# avocado-rev01.net
KiCad netlist of a schematic drawn in EAGLE
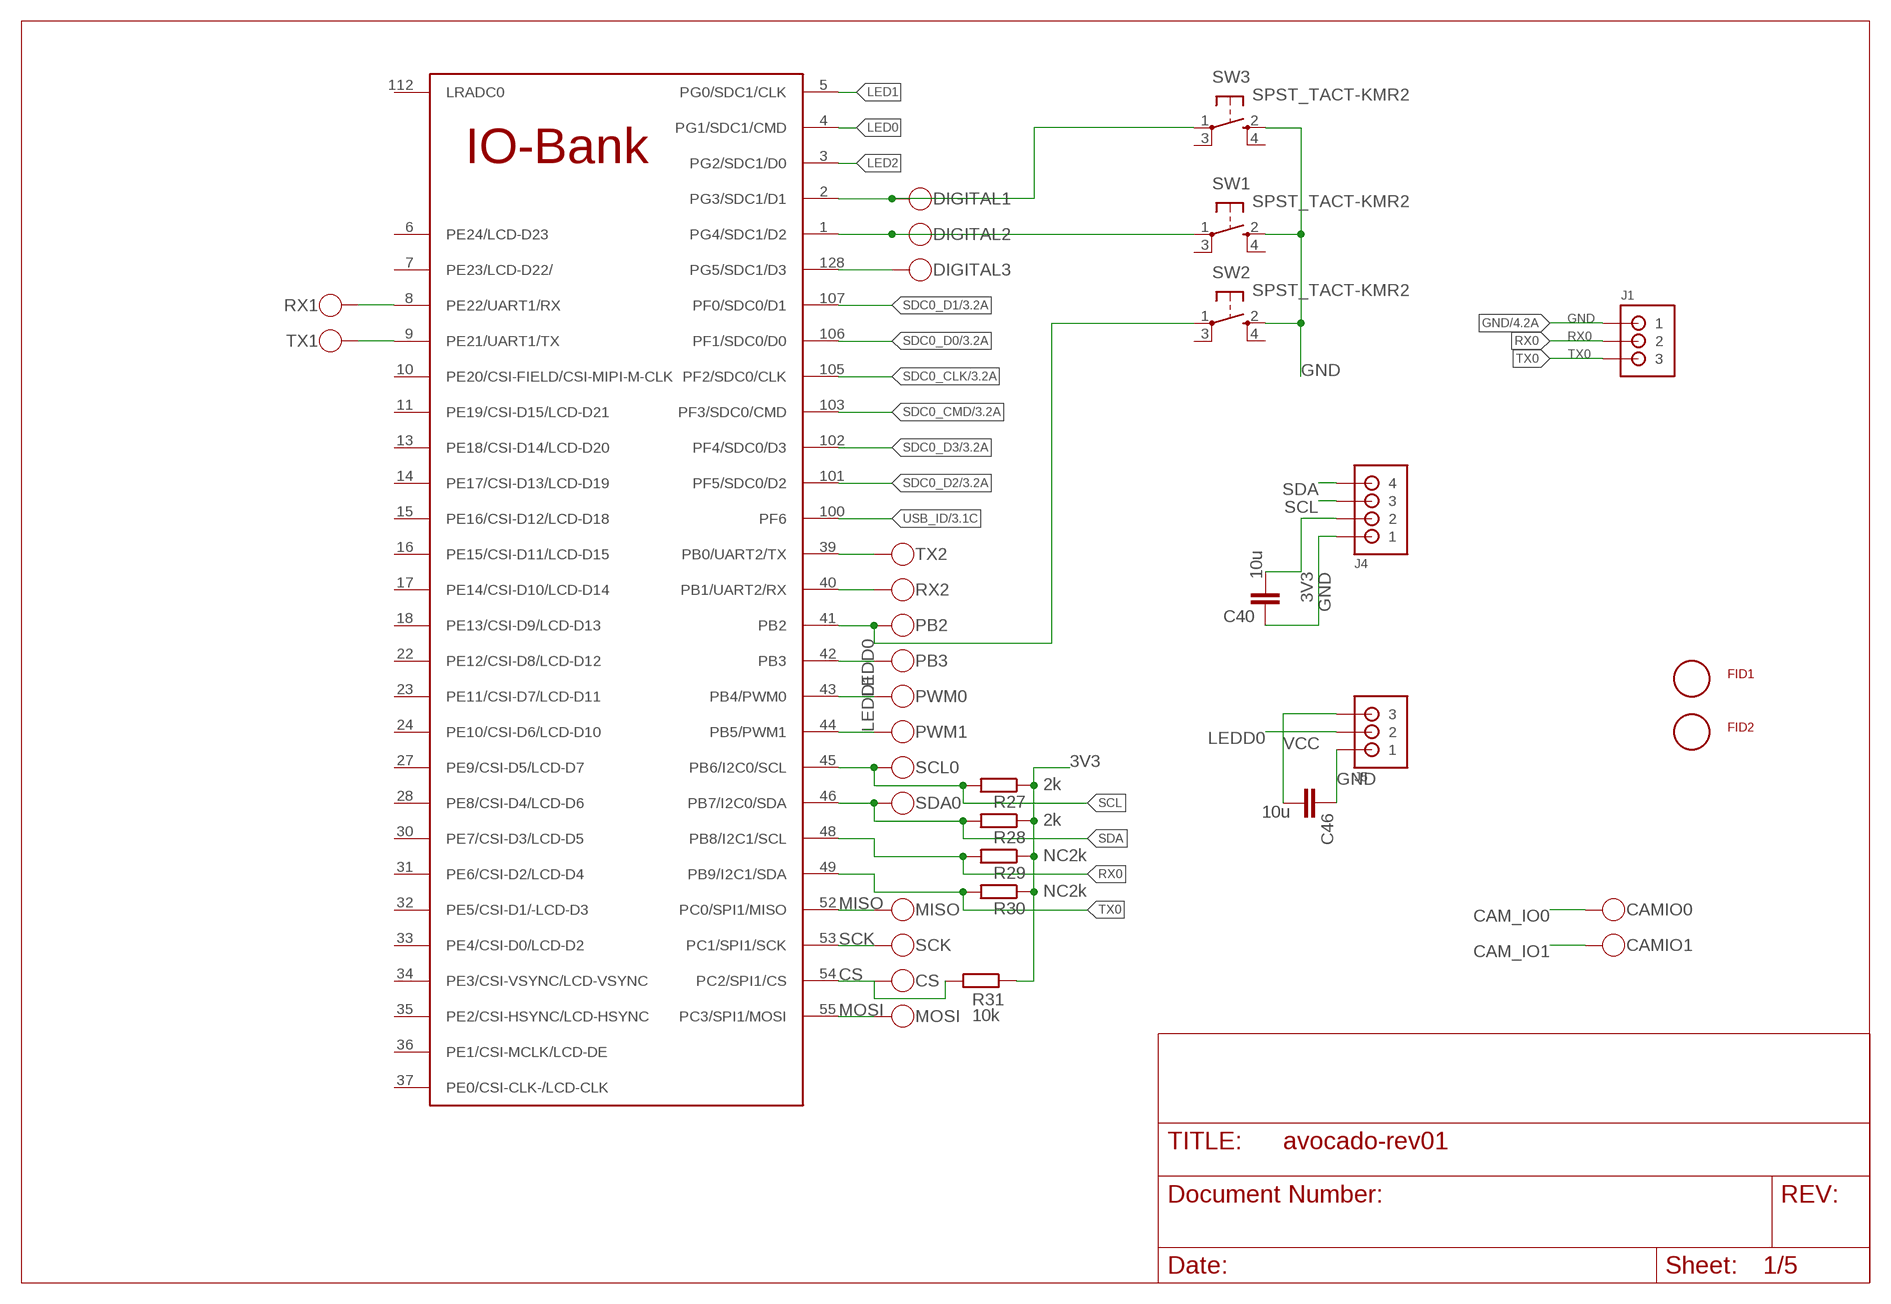
[diagram p0: schematic, sheet 1]
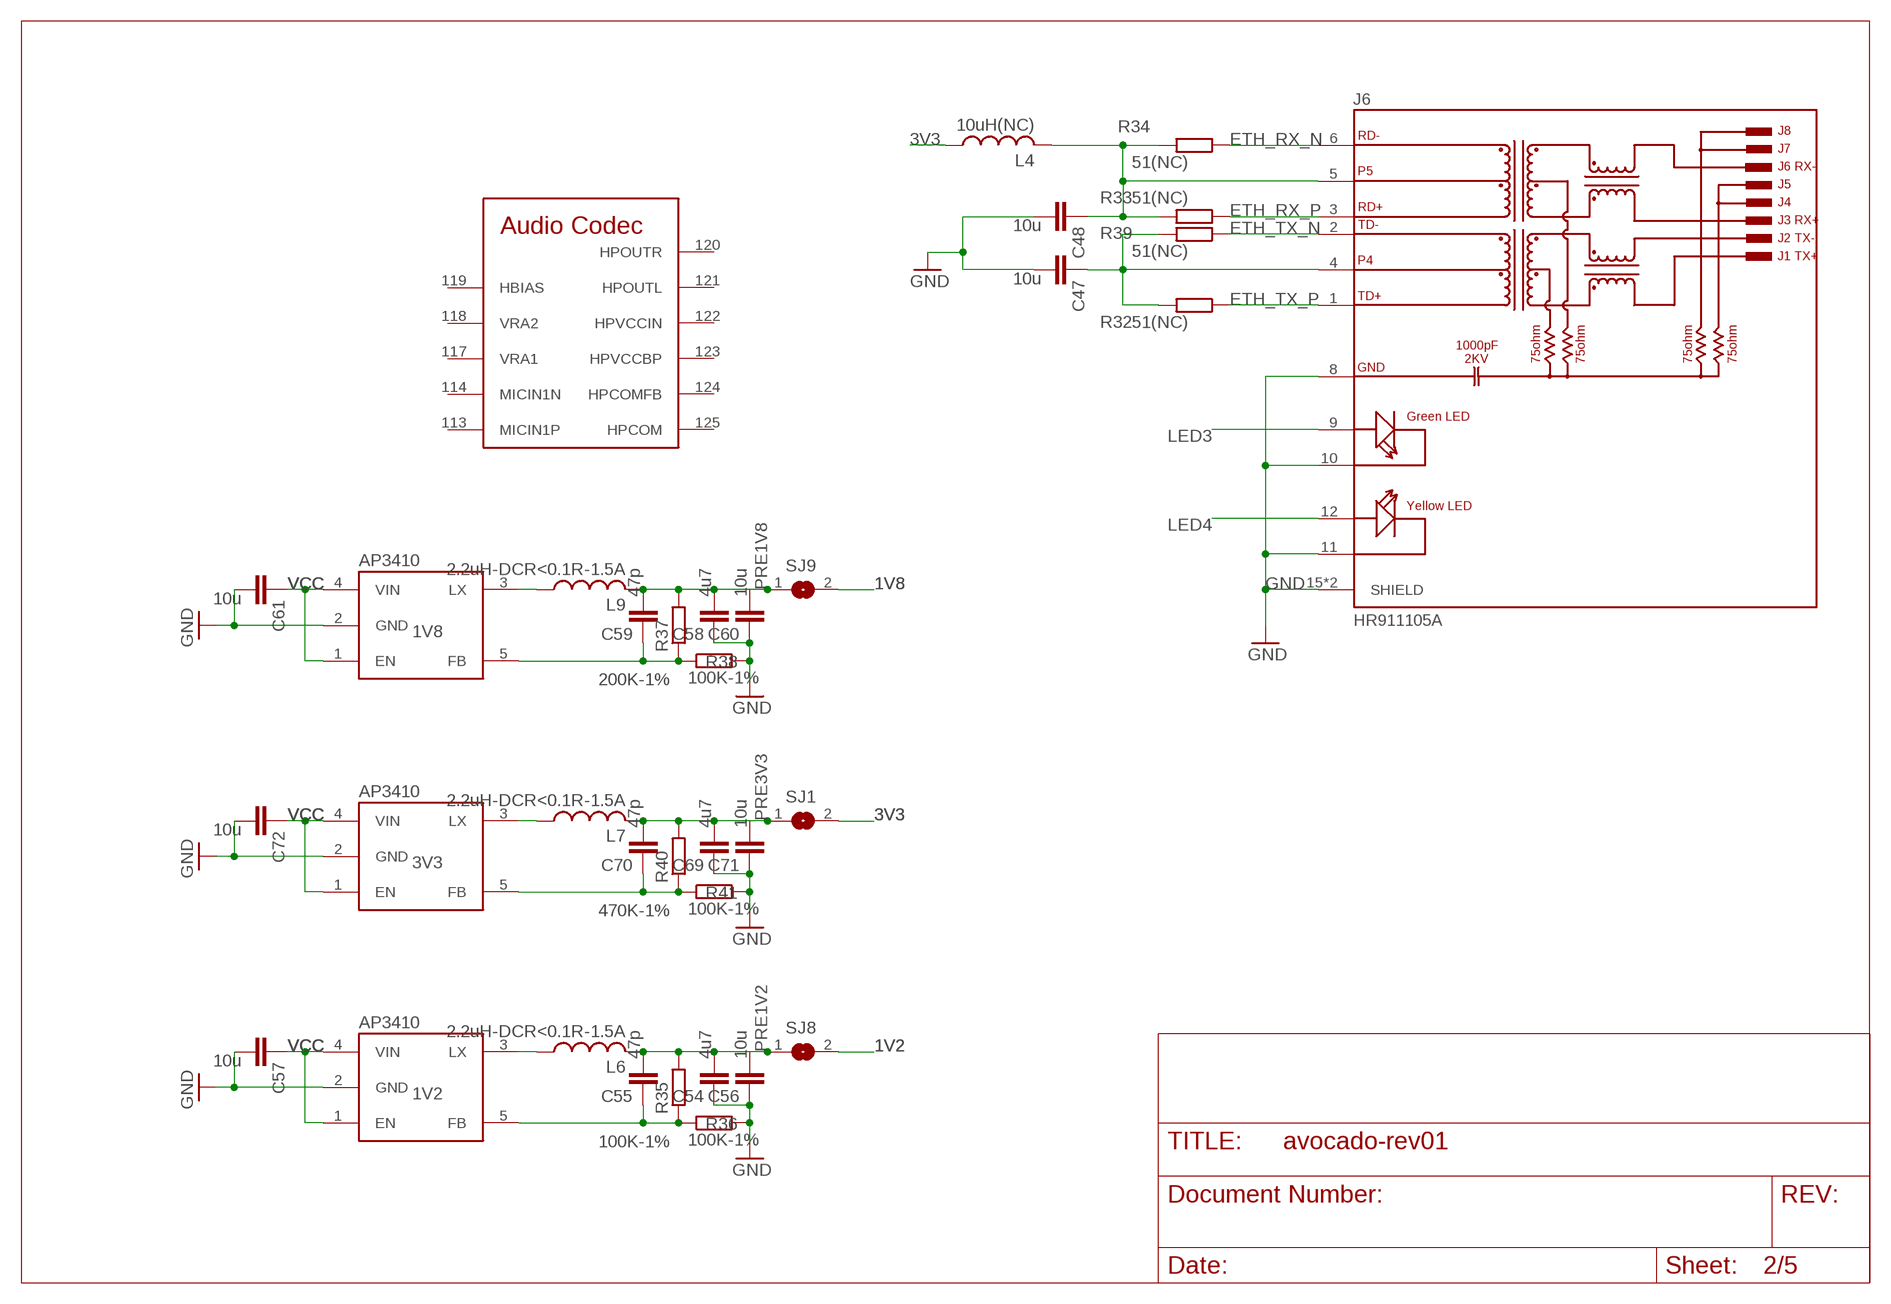
[diagram p1: schematic, sheet 2]
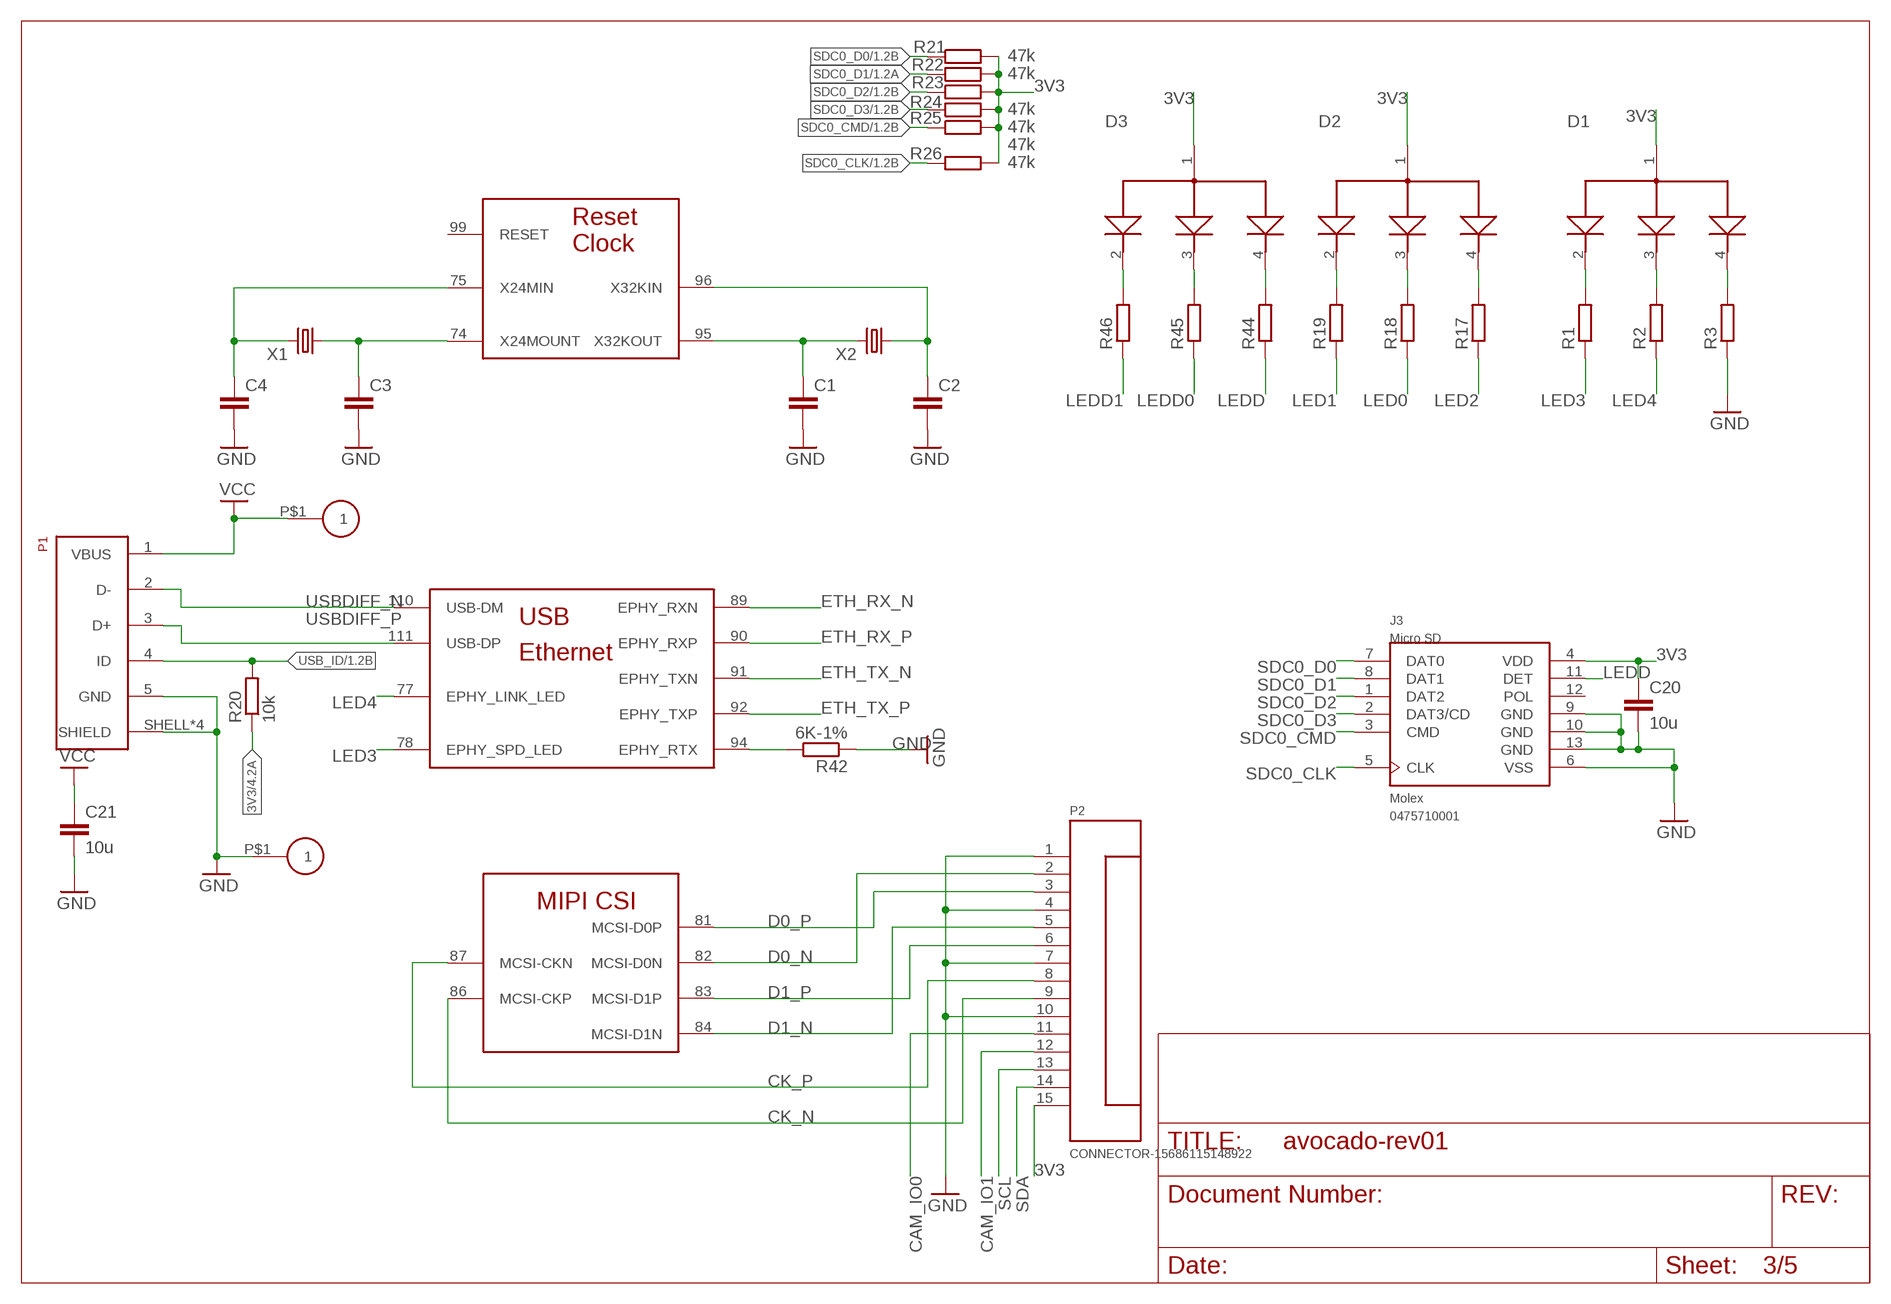
[diagram p2: schematic, sheet 3]
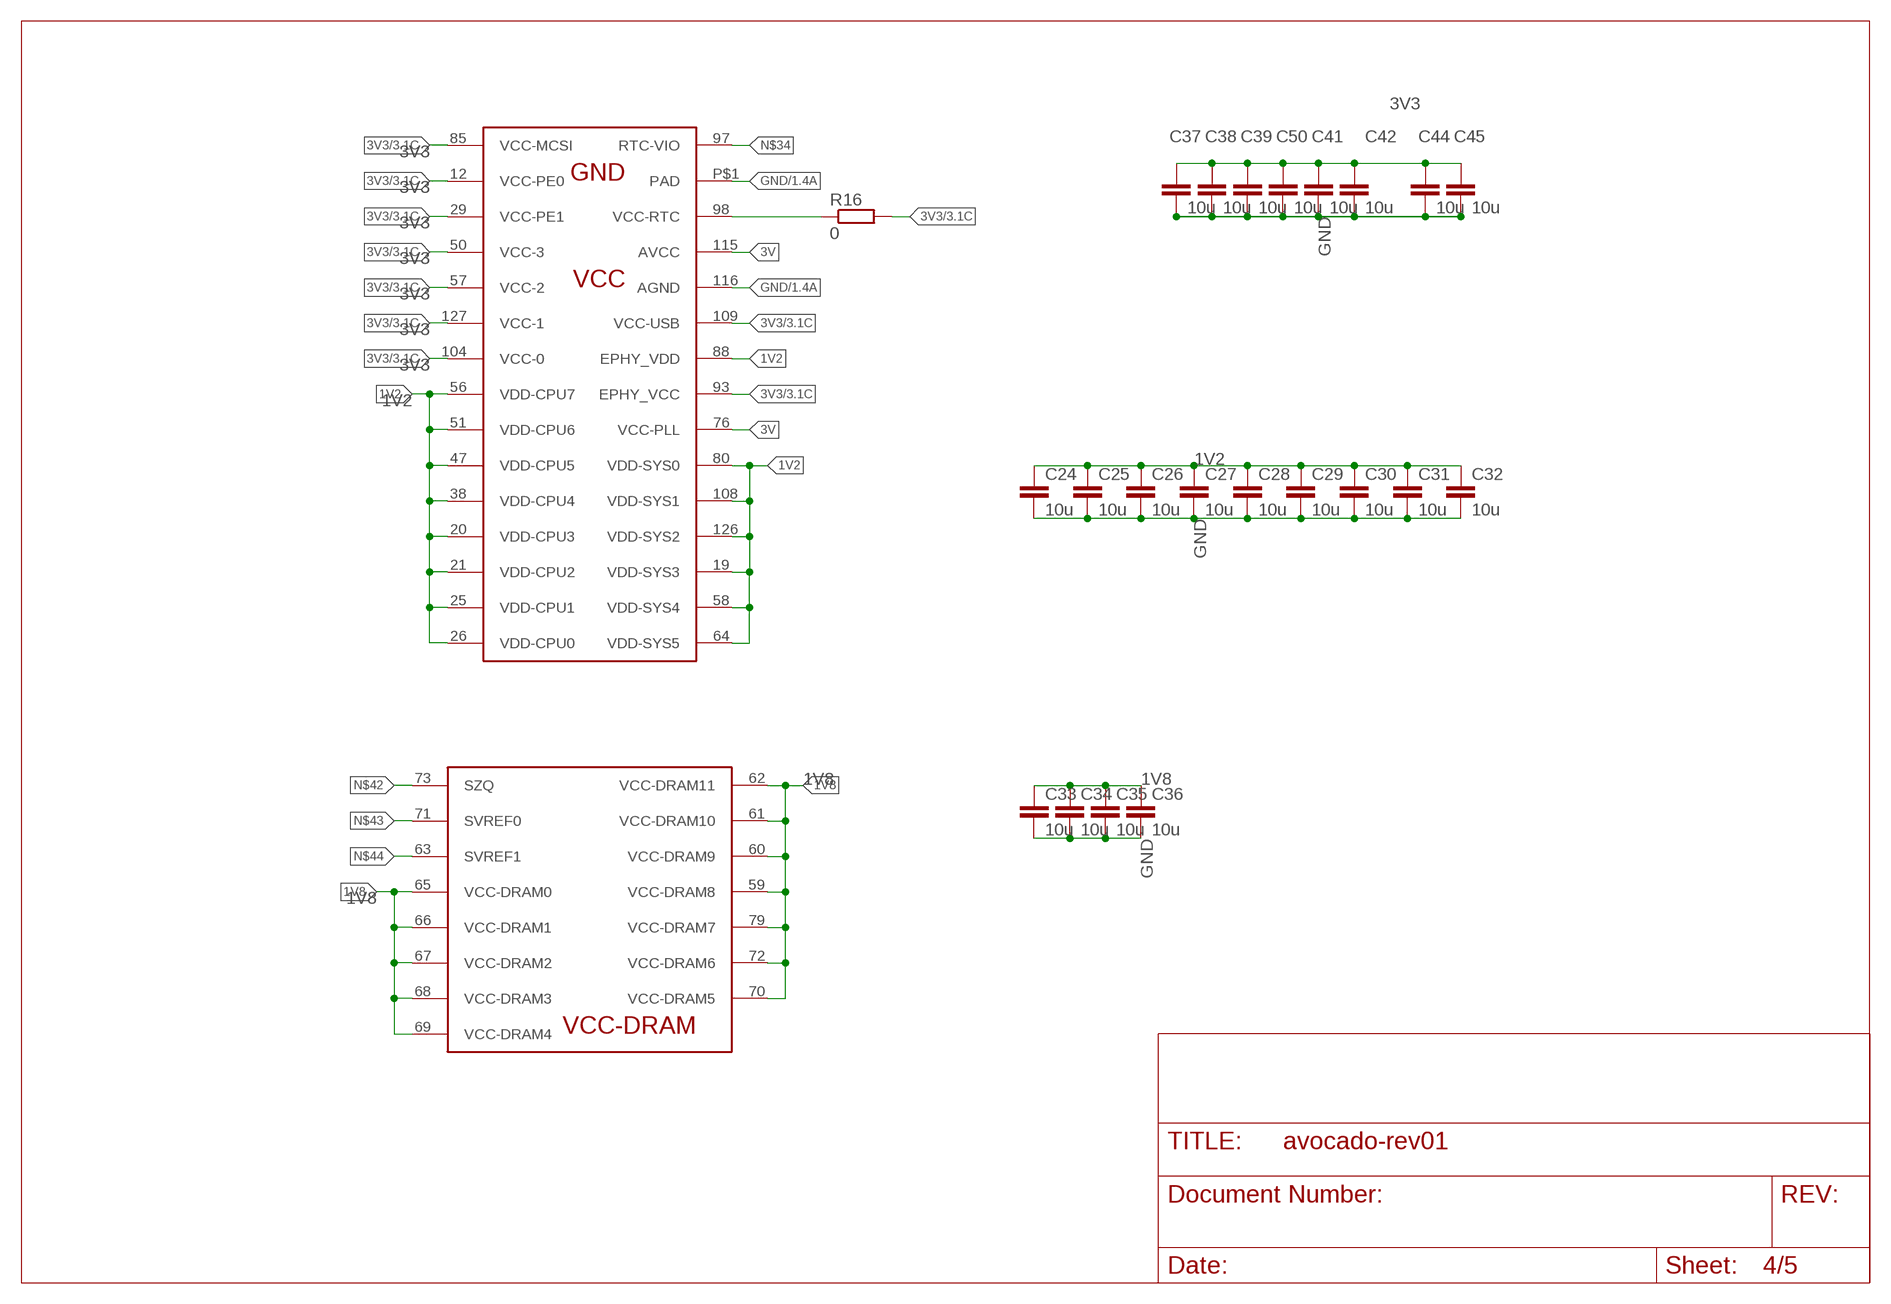
[diagram p3: schematic, sheet 4]
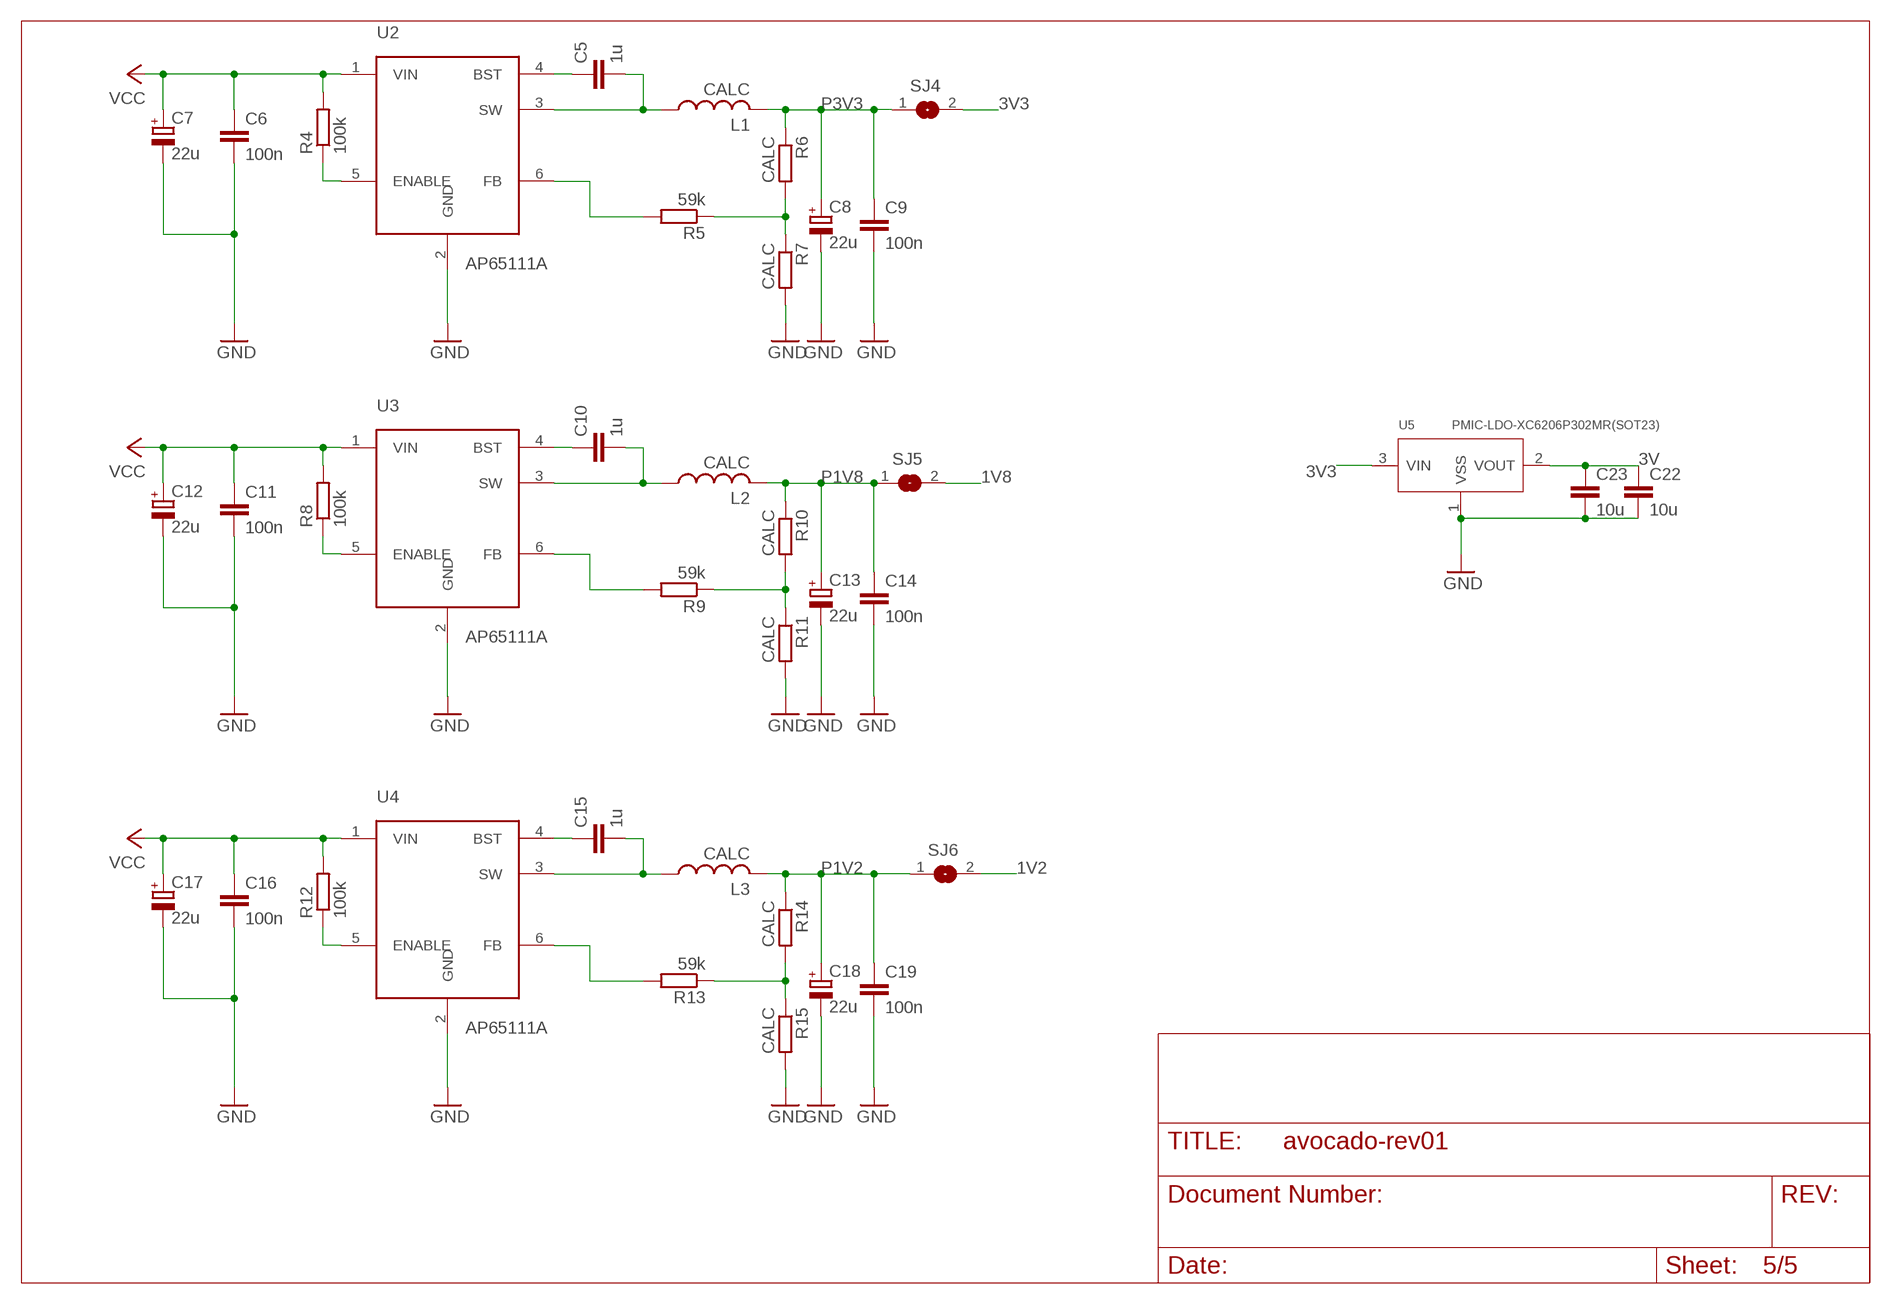
[diagram p4: schematic, sheet 5]

(export (version "E")
  (design (tool "Eeschema 10.0.6"))
  (components
    (comp (ref "C47")
      (value "10u")
      (footprint "eagle-import:C0603")
      (libsource (lib "eagle-import") (part "C0603"))
    )
    (comp (ref "C48")
      (value "10u")
      (footprint "eagle-import:C0603")
      (libsource (lib "eagle-import") (part "C0603"))
    )
    (comp (ref "C54")
      (value "4u7")
      (footprint "eagle-import:C0603")
      (libsource (lib "eagle-import") (part "C0603"))
    )
    (comp (ref "C55")
      (value "47p")
      (footprint "eagle-import:C0603")
      (libsource (lib "eagle-import") (part "C0603"))
    )
    (comp (ref "C56")
      (value "10u")
      (footprint "eagle-import:C0603")
      (libsource (lib "eagle-import") (part "C0603"))
    )
    (comp (ref "C57")
      (value "10u")
      (footprint "eagle-import:C0603")
      (libsource (lib "eagle-import") (part "C0603"))
    )
    (comp (ref "C58")
      (value "4u7")
      (footprint "eagle-import:C0603")
      (libsource (lib "eagle-import") (part "C0603"))
    )
    (comp (ref "C59")
      (value "47p")
      (footprint "eagle-import:C0603")
      (libsource (lib "eagle-import") (part "C0603"))
    )
    (comp (ref "C60")
      (value "10u")
      (footprint "eagle-import:C0603")
      (libsource (lib "eagle-import") (part "C0603"))
    )
    (comp (ref "C61")
      (value "10u")
      (footprint "eagle-import:C0603")
      (libsource (lib "eagle-import") (part "C0603"))
    )
    (comp (ref "C69")
      (value "4u7")
      (footprint "eagle-import:C0603")
      (libsource (lib "eagle-import") (part "C0603"))
    )
    (comp (ref "C70")
      (value "47p")
      (footprint "eagle-import:C0603")
      (libsource (lib "eagle-import") (part "C0603"))
    )
    (comp (ref "C71")
      (value "10u")
      (footprint "eagle-import:C0603")
      (libsource (lib "eagle-import") (part "C0603"))
    )
    (comp (ref "C72")
      (value "10u")
      (footprint "eagle-import:C0603")
      (libsource (lib "eagle-import") (part "C0603"))
    )
    (comp (ref "IC2")
      (value "3V#")
      (footprint "eagle-import:SOT23-5L")
      (fields (field (name "MPN") "AP3410KTR-G1 ") (field (name "VOLTAGE") "3V3"))
      (libsource (lib "eagle-import") (part "MCP73811/2"))
    )
    (comp (ref "IC5")
      (value "3V#")
      (footprint "eagle-import:SOT23-5L")
      (fields (field (name "VOLTAGE") "1V2"))
      (libsource (lib "eagle-import") (part "MCP73811/2"))
    )
    (comp (ref "IC6")
      (value "MCP73811/2")
      (footprint "eagle-import:SOT23-5L")
      (fields (field (name "MPN") "AP3410KTR-G1 ") (field (name "VOLTAGE") "1V8"))
      (libsource (lib "eagle-import") (part "MCP73811/2"))
    )
    (comp (ref "J6")
      (value "HR911105A")
      (footprint "eagle-import:HANRUN_HR911105A")
      (fields (field (name "MF") "HanRun"))
      (libsource (lib "eagle-import") (part "HR911105A"))
    )
    (comp (ref "L4")
      (value "10uH(NC)")
      (footprint "eagle-import:R0603")
      (fields (field (name "MPN") "BLM18BD601SN1D") (field (name "MPN_1") " LVF404018-2R2M-N"))
      (libsource (lib "eagle-import") (part "L0603"))
    )
    (comp (ref "L6")
      (value "2.2uH-DCR<0.1R-1.5A")
      (footprint "eagle-import:ASPI-4030S-253675")
      (fields
        (field (name "MPN") "ASPI-4030S-253675")
        (field (name "MOUSER") " LVF404018-2R2M-N")
        (field (name "MPN_1") " LVF404018-2R2M-N")
      )
      (libsource (lib "eagle-import") (part "L4X4"))
    )
    (comp (ref "L7")
      (value "2.2uH-DCR<0.1R-1.5A")
      (footprint "eagle-import:ASPI-4030S-253675")
      (fields
        (field (name "MPN") "ASPI-4030S-253675")
        (field (name "MOUSER") " LVF404018-2R2M-N")
        (field (name "MPN_1") " LVF404018-2R2M-N")
      )
      (libsource (lib "eagle-import") (part "L4X4"))
    )
    (comp (ref "L9")
      (value "2.2uH-DCR<0.1R-1.5A")
      (footprint "eagle-import:ASPI-4030S-253675")
      (fields
        (field (name "MPN") "ASPI-4030S-253675")
        (field (name "MOUSER") " LVF404018-2R2M-N")
        (field (name "MPN_1") " LVF404018-2R2M-N")
      )
      (libsource (lib "eagle-import") (part "L4X4"))
    )
    (comp (ref "R32")
      (value "51(NC)")
      (footprint "eagle-import:R0402")
      (libsource (lib "eagle-import") (part "R-EU_R0402"))
    )
    (comp (ref "R33")
      (value "51(NC)")
      (footprint "eagle-import:R0402")
      (libsource (lib "eagle-import") (part "R-EU_R0402"))
    )
    (comp (ref "R34")
      (value "51(NC)")
      (footprint "eagle-import:R0402")
      (libsource (lib "eagle-import") (part "R-EU_R0402"))
    )
    (comp (ref "R35")
      (value "100K-1%")
      (footprint "eagle-import:R0402")
      (libsource (lib "eagle-import") (part "R-EU_R0402"))
    )
    (comp (ref "R36")
      (value "100K-1%")
      (footprint "eagle-import:R0402")
      (libsource (lib "eagle-import") (part "R-EU_R0402"))
    )
    (comp (ref "R37")
      (value "200K-1%")
      (footprint "eagle-import:R0402")
      (libsource (lib "eagle-import") (part "R-EU_R0402"))
    )
    (comp (ref "R38")
      (value "100K-1%")
      (footprint "eagle-import:R0402")
      (libsource (lib "eagle-import") (part "R-EU_R0402"))
    )
    (comp (ref "R39")
      (value "51(NC)")
      (footprint "eagle-import:R0402")
      (libsource (lib "eagle-import") (part "R-EU_R0402"))
    )
    (comp (ref "R40")
      (value "470K-1%")
      (footprint "eagle-import:R0402")
      (libsource (lib "eagle-import") (part "R-EU_R0402"))
    )
    (comp (ref "R41")
      (value "100K-1%")
      (footprint "eagle-import:R0402")
      (libsource (lib "eagle-import") (part "R-EU_R0402"))
    )
    (comp (ref "SJ1") (value "SJ") (footprint "eagle-import:SJ") (libsource (lib "eagle-import") (part "SJ")))
    (comp (ref "SJ8") (value "SJ") (footprint "eagle-import:SJ") (libsource (lib "eagle-import") (part "SJ")))
    (comp (ref "SJ9") (value "SJ") (footprint "eagle-import:SJ") (libsource (lib "eagle-import") (part "SJ")))
    (comp (ref "U1")
      (value "V3S")
      (footprint "eagle-import:QFP-128")
      (fields (field (name "MPN") "V3s"))
      (libsource (lib "eagle-import") (part "V3S"))
    )
    (comp (ref "C40")
      (value "10u")
      (footprint "eagle-import:C0603")
      (libsource (lib "eagle-import") (part "C0603"))
    )
    (comp (ref "C46")
      (value "10u")
      (footprint "eagle-import:C0603")
      (libsource (lib "eagle-import") (part "C0603"))
    )
    (comp (ref "CAMIO0")
      (value "TEST_TESTPOINT")
      (footprint "eagle-import:TEST_TESTPOINT")
      (libsource (lib "eagle-import") (part "TEST_TESTPOINT"))
    )
    (comp (ref "CAMIO1")
      (value "TEST_TESTPOINT")
      (footprint "eagle-import:TEST_TESTPOINT")
      (libsource (lib "eagle-import") (part "TEST_TESTPOINT"))
    )
    (comp (ref "CS")
      (value "TEST_TESTPOINT")
      (footprint "eagle-import:TEST_TESTPOINT")
      (libsource (lib "eagle-import") (part "TEST_TESTPOINT"))
    )
    (comp (ref "DIGITAL1")
      (value "TEST_TESTPOINT")
      (footprint "eagle-import:TEST_TESTPOINT")
      (libsource (lib "eagle-import") (part "TEST_TESTPOINT"))
    )
    (comp (ref "DIGITAL2")
      (value "TEST_TESTPOINT")
      (footprint "eagle-import:TEST_TESTPOINT")
      (libsource (lib "eagle-import") (part "TEST_TESTPOINT"))
    )
    (comp (ref "DIGITAL3")
      (value "TEST_TESTPOINT")
      (footprint "eagle-import:TEST_TESTPOINT")
      (libsource (lib "eagle-import") (part "TEST_TESTPOINT"))
    )
    (comp (ref "FID1")
      (value "FIDUCIAL")
      (footprint "eagle-import:FIDUCIAL_1MM")
      (libsource (lib "eagle-import") (part "FIDUCIAL"))
    )
    (comp (ref "FID2")
      (value "FIDUCIAL")
      (footprint "eagle-import:FIDUCIAL_1MM")
      (libsource (lib "eagle-import") (part "FIDUCIAL"))
    )
    (comp (ref "J1")
      (value "CONNECTOR-3HEADER3")
      (footprint "eagle-import:HEADER-3")
      (libsource (lib "eagle-import") (part "marius_5910807_CONNECTOR-3HEADER3"))
    )
    (comp (ref "J4")
      (value "CONNECTOR-4HEADER4")
      (footprint "eagle-import:HEADER-4")
      (fields (field (name "MPN") "7-338069-4"))
      (libsource (lib "eagle-import") (part "CONNECTOR-4HEADER4"))
    )
    (comp (ref "J5")
      (value "CONNECTOR-3HEADER3")
      (footprint "eagle-import:HEADER-3")
      (libsource (lib "eagle-import") (part "CONNECTOR-3HEADER3"))
    )
    (comp (ref "MISO")
      (value "TEST_TESTPOINT")
      (footprint "eagle-import:TEST_TESTPOINT")
      (libsource (lib "eagle-import") (part "TEST_TESTPOINT"))
    )
    (comp (ref "MOSI")
      (value "TEST_TESTPOINT")
      (footprint "eagle-import:TEST_TESTPOINT")
      (libsource (lib "eagle-import") (part "TEST_TESTPOINT"))
    )
    (comp (ref "PB2")
      (value "TEST_TESTPOINT")
      (footprint "eagle-import:TEST_TESTPOINT")
      (libsource (lib "eagle-import") (part "TEST_TESTPOINT"))
    )
    (comp (ref "PB3")
      (value "TEST_TESTPOINT")
      (footprint "eagle-import:TEST_TESTPOINT")
      (libsource (lib "eagle-import") (part "TEST_TESTPOINT"))
    )
    (comp (ref "PWM0")
      (value "TEST_TESTPOINT")
      (footprint "eagle-import:TEST_TESTPOINT")
      (libsource (lib "eagle-import") (part "TEST_TESTPOINT"))
    )
    (comp (ref "PWM1")
      (value "TEST_TESTPOINT")
      (footprint "eagle-import:TEST_TESTPOINT")
      (libsource (lib "eagle-import") (part "TEST_TESTPOINT"))
    )
    (comp (ref "R27")
      (value "2k")
      (footprint "eagle-import:R0402")
      (libsource (lib "eagle-import") (part "R-EU_R0402"))
    )
    (comp (ref "R28")
      (value "2k")
      (footprint "eagle-import:R0402")
      (libsource (lib "eagle-import") (part "R-EU_R0402"))
    )
    (comp (ref "R29")
      (value "NC2k")
      (footprint "eagle-import:R0402")
      (libsource (lib "eagle-import") (part "R-EU_R0402"))
    )
    (comp (ref "R30")
      (value "NC2k")
      (footprint "eagle-import:R0402")
      (libsource (lib "eagle-import") (part "R-EU_R0402"))
    )
    (comp (ref "R31")
      (value "10k")
      (footprint "eagle-import:R0402")
      (libsource (lib "eagle-import") (part "R-EU_R0402"))
    )
    (comp (ref "RX1")
      (value "TEST_TESTPOINT")
      (footprint "eagle-import:TEST_TESTPOINT")
      (libsource (lib "eagle-import") (part "TEST_TESTPOINT"))
    )
    (comp (ref "RX2")
      (value "TEST_TESTPOINT")
      (footprint "eagle-import:TEST_TESTPOINT")
      (libsource (lib "eagle-import") (part "TEST_TESTPOINT"))
    )
    (comp (ref "SCK")
      (value "TEST_TESTPOINT")
      (footprint "eagle-import:TEST_TESTPOINT")
      (libsource (lib "eagle-import") (part "TEST_TESTPOINT"))
    )
    (comp (ref "SCL0")
      (value "TEST_TESTPOINT")
      (footprint "eagle-import:TEST_TESTPOINT")
      (libsource (lib "eagle-import") (part "TEST_TESTPOINT"))
    )
    (comp (ref "SDA0")
      (value "TEST_TESTPOINT")
      (footprint "eagle-import:TEST_TESTPOINT")
      (libsource (lib "eagle-import") (part "TEST_TESTPOINT"))
    )
    (comp (ref "SW1")
      (value "SPST_TACT-KMR2")
      (footprint "eagle-import:KMR2")
      (libsource (lib "eagle-import") (part "SPST_TACT-KMR2"))
    )
    (comp (ref "SW2")
      (value "SPST_TACT-KMR2")
      (footprint "eagle-import:KMR2")
      (libsource (lib "eagle-import") (part "SPST_TACT-KMR2"))
    )
    (comp (ref "SW3")
      (value "SPST_TACT-KMR2")
      (footprint "eagle-import:KMR2")
      (libsource (lib "eagle-import") (part "SPST_TACT-KMR2"))
    )
    (comp (ref "TX1")
      (value "TEST_TESTPOINT")
      (footprint "eagle-import:TEST_TESTPOINT")
      (libsource (lib "eagle-import") (part "TEST_TESTPOINT"))
    )
    (comp (ref "TX2")
      (value "TEST_TESTPOINT")
      (footprint "eagle-import:TEST_TESTPOINT")
      (libsource (lib "eagle-import") (part "TEST_TESTPOINT"))
    )
    (comp (ref "C24")
      (value "10u")
      (footprint "eagle-import:C0603")
      (libsource (lib "eagle-import") (part "C0603"))
    )
    (comp (ref "C25")
      (value "10u")
      (footprint "eagle-import:C0603")
      (libsource (lib "eagle-import") (part "C0603"))
    )
    (comp (ref "C26")
      (value "10u")
      (footprint "eagle-import:C0603")
      (libsource (lib "eagle-import") (part "C0603"))
    )
    (comp (ref "C27")
      (value "10u")
      (footprint "eagle-import:C0603")
      (libsource (lib "eagle-import") (part "C0603"))
    )
    (comp (ref "C28")
      (value "10u")
      (footprint "eagle-import:C0603")
      (libsource (lib "eagle-import") (part "C0603"))
    )
    (comp (ref "C29")
      (value "10u")
      (footprint "eagle-import:C0603")
      (libsource (lib "eagle-import") (part "C0603"))
    )
    (comp (ref "C30")
      (value "10u")
      (footprint "eagle-import:C0603")
      (libsource (lib "eagle-import") (part "C0603"))
    )
    (comp (ref "C31")
      (value "10u")
      (footprint "eagle-import:C0603")
      (libsource (lib "eagle-import") (part "C0603"))
    )
    (comp (ref "C32")
      (value "10u")
      (footprint "eagle-import:C0603")
      (libsource (lib "eagle-import") (part "C0603"))
    )
    (comp (ref "C33")
      (value "10u")
      (footprint "eagle-import:C0603")
      (libsource (lib "eagle-import") (part "C0603"))
    )
    (comp (ref "C34")
      (value "10u")
      (footprint "eagle-import:C0603")
      (libsource (lib "eagle-import") (part "C0603"))
    )
    (comp (ref "C35")
      (value "10u")
      (footprint "eagle-import:C0603")
      (libsource (lib "eagle-import") (part "C0603"))
    )
    (comp (ref "C36")
      (value "10u")
      (footprint "eagle-import:C0603")
      (libsource (lib "eagle-import") (part "C0603"))
    )
    (comp (ref "C37")
      (value "10u")
      (footprint "eagle-import:C0603")
      (libsource (lib "eagle-import") (part "C0603"))
    )
    (comp (ref "C38")
      (value "10u")
      (footprint "eagle-import:C0603")
      (libsource (lib "eagle-import") (part "C0603"))
    )
    (comp (ref "C39")
      (value "10u")
      (footprint "eagle-import:C0603")
      (libsource (lib "eagle-import") (part "C0603"))
    )
    (comp (ref "C41")
      (value "10u")
      (footprint "eagle-import:C0603")
      (libsource (lib "eagle-import") (part "C0603"))
    )
    (comp (ref "C42")
      (value "10u")
      (footprint "eagle-import:C0603")
      (libsource (lib "eagle-import") (part "C0603"))
    )
    (comp (ref "C44")
      (value "10u")
      (footprint "eagle-import:C0603")
      (libsource (lib "eagle-import") (part "C0603"))
    )
    (comp (ref "C45")
      (value "10u")
      (footprint "eagle-import:C0603")
      (libsource (lib "eagle-import") (part "C0603"))
    )
    (comp (ref "C50")
      (value "10u")
      (footprint "eagle-import:C0603")
      (libsource (lib "eagle-import") (part "C0603"))
    )
    (comp (ref "R16")
      (value "0")
      (footprint "eagle-import:R0603")
      (libsource (lib "eagle-import") (part "R0603"))
    )
    (comp (ref "C5")
      (value "1u")
      (footprint "eagle-import:C0603")
      (libsource (lib "eagle-import") (part "C0603"))
    )
    (comp (ref "C6")
      (value "100n")
      (footprint "eagle-import:C0603")
      (libsource (lib "eagle-import") (part "C0603"))
    )
    (comp (ref "C7")
      (value "22u")
      (footprint "eagle-import:CAP4.3X6.1")
      (libsource (lib "eagle-import") (part "C_POL4.3"))
    )
    (comp (ref "C8")
      (value "22u")
      (footprint "eagle-import:CAP4.3X6.1")
      (libsource (lib "eagle-import") (part "C_POL4.3"))
    )
    (comp (ref "C9")
      (value "100n")
      (footprint "eagle-import:C0603")
      (libsource (lib "eagle-import") (part "C0603"))
    )
    (comp (ref "C10")
      (value "1u")
      (footprint "eagle-import:C0603")
      (libsource (lib "eagle-import") (part "C0603"))
    )
    (comp (ref "C11")
      (value "100n")
      (footprint "eagle-import:C0603")
      (libsource (lib "eagle-import") (part "C0603"))
    )
    (comp (ref "C12")
      (value "22u")
      (footprint "eagle-import:CAP4.3X6.1")
      (libsource (lib "eagle-import") (part "C_POL4.3"))
    )
    (comp (ref "C13")
      (value "22u")
      (footprint "eagle-import:CAP4.3X6.1")
      (libsource (lib "eagle-import") (part "C_POL4.3"))
    )
    (comp (ref "C14")
      (value "100n")
      (footprint "eagle-import:C0603")
      (libsource (lib "eagle-import") (part "C0603"))
    )
    (comp (ref "C15")
      (value "1u")
      (footprint "eagle-import:C0603")
      (libsource (lib "eagle-import") (part "C0603"))
    )
    (comp (ref "C16")
      (value "100n")
      (footprint "eagle-import:C0603")
      (libsource (lib "eagle-import") (part "C0603"))
    )
    (comp (ref "C17")
      (value "22u")
      (footprint "eagle-import:CAP4.3X6.1")
      (libsource (lib "eagle-import") (part "C_POL4.3"))
    )
    (comp (ref "C18")
      (value "22u")
      (footprint "eagle-import:CAP4.3X6.1")
      (libsource (lib "eagle-import") (part "C_POL4.3"))
    )
    (comp (ref "C19")
      (value "100n")
      (footprint "eagle-import:C0603")
      (libsource (lib "eagle-import") (part "C0603"))
    )
    (comp (ref "C22")
      (value "10u")
      (footprint "eagle-import:C0603")
      (libsource (lib "eagle-import") (part "C0603"))
    )
    (comp (ref "C23")
      (value "10u")
      (footprint "eagle-import:C0603")
      (libsource (lib "eagle-import") (part "C0603"))
    )
    (comp (ref "L1")
      (value "CALC")
      (footprint "eagle-import:B82462A4153K")
      (fields (field (name "MPN") "B82462A4153K"))
      (libsource (lib "eagle-import") (part "L6X6"))
    )
    (comp (ref "L2")
      (value "CALC")
      (footprint "eagle-import:B82462A4153K")
      (fields (field (name "MPN") "B82462A4153K"))
      (libsource (lib "eagle-import") (part "L6X6"))
    )
    (comp (ref "L3")
      (value "CALC")
      (footprint "eagle-import:B82462A4153K")
      (fields (field (name "MPN") "B82462A4153K"))
      (libsource (lib "eagle-import") (part "L6X6"))
    )
    (comp (ref "R4")
      (value "100k")
      (footprint "eagle-import:R0603")
      (libsource (lib "eagle-import") (part "R0603"))
    )
    (comp (ref "R5")
      (value "59k")
      (footprint "eagle-import:R0603")
      (libsource (lib "eagle-import") (part "R0603"))
    )
    (comp (ref "R6")
      (value "CALC")
      (footprint "eagle-import:R0603")
      (libsource (lib "eagle-import") (part "R0603"))
    )
    (comp (ref "R7")
      (value "CALC")
      (footprint "eagle-import:R0603")
      (libsource (lib "eagle-import") (part "R0603"))
    )
    (comp (ref "R8")
      (value "100k")
      (footprint "eagle-import:R0603")
      (libsource (lib "eagle-import") (part "R0603"))
    )
    (comp (ref "R9")
      (value "59k")
      (footprint "eagle-import:R0603")
      (libsource (lib "eagle-import") (part "R0603"))
    )
    (comp (ref "R10")
      (value "CALC")
      (footprint "eagle-import:R0603")
      (libsource (lib "eagle-import") (part "R0603"))
    )
    (comp (ref "R11")
      (value "CALC")
      (footprint "eagle-import:R0603")
      (libsource (lib "eagle-import") (part "R0603"))
    )
    (comp (ref "R12")
      (value "100k")
      (footprint "eagle-import:R0603")
      (libsource (lib "eagle-import") (part "R0603"))
    )
    (comp (ref "R13")
      (value "59k")
      (footprint "eagle-import:R0603")
      (libsource (lib "eagle-import") (part "R0603"))
    )
    (comp (ref "R14")
      (value "CALC")
      (footprint "eagle-import:R0603")
      (libsource (lib "eagle-import") (part "R0603"))
    )
    (comp (ref "R15")
      (value "CALC")
      (footprint "eagle-import:R0603")
      (libsource (lib "eagle-import") (part "R0603"))
    )
    (comp (ref "SJ4") (value "SJ") (footprint "eagle-import:SJ") (libsource (lib "eagle-import") (part "SJ")))
    (comp (ref "SJ5") (value "SJ") (footprint "eagle-import:SJ") (libsource (lib "eagle-import") (part "SJ")))
    (comp (ref "SJ6") (value "SJ") (footprint "eagle-import:SJ") (libsource (lib "eagle-import") (part "SJ")))
    (comp (ref "U2")
      (value "AP65111A")
      (footprint "eagle-import:TSOT26")
      (fields (field (name "MPN") "AP65111AWU-7"))
      (libsource (lib "eagle-import") (part "AP65111A"))
    )
    (comp (ref "U3")
      (value "AP65111A")
      (footprint "eagle-import:TSOT26")
      (fields (field (name "MPN") "AP65111AWU-7"))
      (libsource (lib "eagle-import") (part "AP65111A"))
    )
    (comp (ref "U4")
      (value "AP65111A")
      (footprint "eagle-import:TSOT26")
      (fields (field (name "MPN") "AP65111AWU-7"))
      (libsource (lib "eagle-import") (part "AP65111A"))
    )
    (comp (ref "U5")
      (value "PMIC-LDO-XC6206P302MR(SOT23)")
      (footprint "eagle-import:SOT-23")
      (description "N/A")
      (fields
        (field (name "MF") "Torex")
        (field (name "MP") "XC6206P302MR")
        (field (name "AVAILABILITY") "N/A")
      )
      (libsource (lib "eagle-import") (part "PMIC-LDO-XC6206P302MR(SOT23)"))
    )
    (comp (ref "5V")
      (value "PADTH")
      (footprint "eagle-import:PAD")
      (libsource (lib "eagle-import") (part "PADTH"))
    )
    (comp (ref "C1")
      (value "C0603")
      (footprint "eagle-import:C0603")
      (libsource (lib "eagle-import") (part "C0603"))
    )
    (comp (ref "C2")
      (value "C0603")
      (footprint "eagle-import:C0603")
      (libsource (lib "eagle-import") (part "C0603"))
    )
    (comp (ref "C3")
      (value "C0603")
      (footprint "eagle-import:C0603")
      (libsource (lib "eagle-import") (part "C0603"))
    )
    (comp (ref "C4")
      (value "C0603")
      (footprint "eagle-import:C0603")
      (libsource (lib "eagle-import") (part "C0603"))
    )
    (comp (ref "C20")
      (value "10u")
      (footprint "eagle-import:C0603")
      (libsource (lib "eagle-import") (part "C0603"))
    )
    (comp (ref "C21")
      (value "10u")
      (footprint "eagle-import:C0603")
      (libsource (lib "eagle-import") (part "C0603"))
    )
    (comp (ref "D1")
      (value "LL-R3528RGBC-008-B")
      (footprint "eagle-import:LED_LL-R3528RGBC-008-B")
      (fields (field (name "MF") "Lucky Light") (field (name "MPN") "HQ67-23A2ARGBC "))
      (libsource (lib "eagle-import") (part "LL-R3528RGBC-008-B"))
    )
    (comp (ref "D2")
      (value "LL-R3528RGBC-008-B")
      (footprint "eagle-import:LED_LL-R3528RGBC-008-B")
      (fields (field (name "MF") "Lucky Light") (field (name "MPN") "HQ67-23A2ARGBC "))
      (libsource (lib "eagle-import") (part "LL-R3528RGBC-008-B"))
    )
    (comp (ref "D3")
      (value "LL-R3528RGBC-008-B")
      (footprint "eagle-import:LED_LL-R3528RGBC-008-B")
      (fields (field (name "MF") "Lucky Light") (field (name "MPN") "HQ67-23A2ARGBC "))
      (libsource (lib "eagle-import") (part "LL-R3528RGBC-008-B"))
    )
    (comp (ref "GND")
      (value "PADTH")
      (footprint "eagle-import:PAD")
      (libsource (lib "eagle-import") (part "PADTH"))
    )
    (comp (ref "J3")
      (value "0475710001")
      (footprint "eagle-import:MOLEX_0475710001")
      (fields (field (name "MF") "Molex"))
      (libsource (lib "eagle-import") (part "0475710001"))
    )
    (comp (ref "P1")
      (value "USB629105150521")
      (footprint "eagle-import:629105150521")
      (libsource (lib "eagle-import") (part "USB629105150521"))
    )
    (comp (ref "P2")
      (value "CONNECTOR-15686115148922")
      (footprint "eagle-import:686115148922")
      (fields (field (name "MPN") "686115148922"))
      (libsource (lib "eagle-import") (part "CONNECTOR-15686115148922"))
    )
    (comp (ref "R1")
      (value "R-EU_R0402")
      (footprint "eagle-import:R0402")
      (libsource (lib "eagle-import") (part "R-EU_R0402"))
    )
    (comp (ref "R2")
      (value "R-EU_R0402")
      (footprint "eagle-import:R0402")
      (libsource (lib "eagle-import") (part "R-EU_R0402"))
    )
    (comp (ref "R3")
      (value "R-EU_R0402")
      (footprint "eagle-import:R0402")
      (libsource (lib "eagle-import") (part "R-EU_R0402"))
    )
    (comp (ref "R17")
      (value "R-EU_R0402")
      (footprint "eagle-import:R0402")
      (libsource (lib "eagle-import") (part "R-EU_R0402"))
    )
    (comp (ref "R18")
      (value "R-EU_R0402")
      (footprint "eagle-import:R0402")
      (libsource (lib "eagle-import") (part "R-EU_R0402"))
    )
    (comp (ref "R19")
      (value "R-EU_R0402")
      (footprint "eagle-import:R0402")
      (libsource (lib "eagle-import") (part "R-EU_R0402"))
    )
    (comp (ref "R20")
      (value "10k")
      (footprint "eagle-import:R0402")
      (libsource (lib "eagle-import") (part "R-EU_R0402"))
    )
    (comp (ref "R21")
      (value "47k")
      (footprint "eagle-import:R0603")
      (libsource (lib "eagle-import") (part "R0603"))
    )
    (comp (ref "R22")
      (value "47k")
      (footprint "eagle-import:R0603")
      (libsource (lib "eagle-import") (part "R0603"))
    )
    (comp (ref "R23")
      (value "47k")
      (footprint "eagle-import:R0603")
      (libsource (lib "eagle-import") (part "R0603"))
    )
    (comp (ref "R24")
      (value "47k")
      (footprint "eagle-import:R0603")
      (libsource (lib "eagle-import") (part "R0603"))
    )
    (comp (ref "R25")
      (value "47k")
      (footprint "eagle-import:R0603")
      (libsource (lib "eagle-import") (part "R0603"))
    )
    (comp (ref "R26")
      (value "47k")
      (footprint "eagle-import:R0603")
      (libsource (lib "eagle-import") (part "R0603"))
    )
    (comp (ref "R42")
      (value "6K-1%")
      (footprint "eagle-import:R0402")
      (libsource (lib "eagle-import") (part "R-EU_R0402"))
    )
    (comp (ref "R44")
      (value "R-EU_R0402")
      (footprint "eagle-import:R0402")
      (libsource (lib "eagle-import") (part "R-EU_R0402"))
    )
    (comp (ref "R45")
      (value "R-EU_R0402")
      (footprint "eagle-import:R0402")
      (libsource (lib "eagle-import") (part "R-EU_R0402"))
    )
    (comp (ref "R46")
      (value "R-EU_R0402")
      (footprint "eagle-import:R0402")
      (libsource (lib "eagle-import") (part "R-EU_R0402"))
    )
    (comp (ref "X1")
      (value "XTAL3.2X2")
      (footprint "eagle-import:3.2X2-4")
      (fields (field (name "MPN") "7U24000E09UCG"))
      (libsource (lib "eagle-import") (part "XTAL3.2X2"))
    )
    (comp (ref "X2")
      (value "XTAL5X1.9")
      (footprint "eagle-import:XTAL-5X1.9")
      (fields (field (name "MPN") "SF32K32768D71T01 "))
      (libsource (lib "eagle-import") (part "XTAL5X1.9"))
    )
  )
  (nets
    (net (code "1") (name "1V2") (class "Default")
      (node (ref "C24") (pin "1") (pinfunction "1_1") (pintype "passive"))
      (node (ref "C25") (pin "1") (pinfunction "1_1") (pintype "passive"))
      (node (ref "C26") (pin "1") (pinfunction "1_1") (pintype "passive"))
      (node (ref "C27") (pin "1") (pinfunction "1_1") (pintype "passive"))
      (node (ref "C28") (pin "1") (pinfunction "1_1") (pintype "passive"))
      (node (ref "C29") (pin "1") (pinfunction "1_1") (pintype "passive"))
      (node (ref "C30") (pin "1") (pinfunction "1_1") (pintype "passive"))
      (node (ref "C31") (pin "1") (pinfunction "1_1") (pintype "passive"))
      (node (ref "C32") (pin "1") (pinfunction "1_1") (pintype "passive"))
      (node (ref "SJ6") (pin "2") (pinfunction "2_2") (pintype "passive"))
      (node (ref "SJ8") (pin "2") (pinfunction "2_2") (pintype "passive"))
      (node (ref "U1") (pin "108") (pinfunction "VDD-SYS1_108") (pintype "bidirectional"))
      (node (ref "U1") (pin "126") (pinfunction "VDD-SYS2_126") (pintype "bidirectional"))
      (node (ref "U1") (pin "19") (pinfunction "VDD-SYS3_19") (pintype "bidirectional"))
      (node (ref "U1") (pin "20") (pinfunction "VDD-CPU3_20") (pintype "bidirectional"))
      (node (ref "U1") (pin "21") (pinfunction "VDD-CPU2_21") (pintype "bidirectional"))
      (node (ref "U1") (pin "25") (pinfunction "VDD-CPU1_25") (pintype "bidirectional"))
      (node (ref "U1") (pin "26") (pinfunction "VDD-CPU0_26") (pintype "bidirectional"))
      (node (ref "U1") (pin "38") (pinfunction "VDD-CPU4_38") (pintype "bidirectional"))
      (node (ref "U1") (pin "47") (pinfunction "VDD-CPU5_47") (pintype "bidirectional"))
      (node (ref "U1") (pin "51") (pinfunction "VDD-CPU6_51") (pintype "bidirectional"))
      (node (ref "U1") (pin "56") (pinfunction "VDD-CPU7_56") (pintype "bidirectional"))
      (node (ref "U1") (pin "58") (pinfunction "VDD-SYS4_58") (pintype "bidirectional"))
      (node (ref "U1") (pin "64") (pinfunction "VDD-SYS5_64") (pintype "bidirectional"))
      (node (ref "U1") (pin "80") (pinfunction "VDD-SYS0_80") (pintype "bidirectional"))
      (node (ref "U1") (pin "88") (pinfunction "EPHY_VDD_88") (pintype "bidirectional"))
    )
    (net (code "2") (name "1V8") (class "Default")
      (node (ref "C33") (pin "1") (pinfunction "1_1") (pintype "passive"))
      (node (ref "C34") (pin "1") (pinfunction "1_1") (pintype "passive"))
      (node (ref "C35") (pin "1") (pinfunction "1_1") (pintype "passive"))
      (node (ref "C36") (pin "1") (pinfunction "1_1") (pintype "passive"))
      (node (ref "SJ5") (pin "2") (pinfunction "2_2") (pintype "passive"))
      (node (ref "SJ9") (pin "2") (pinfunction "2_2") (pintype "passive"))
      (node (ref "U1") (pin "59") (pinfunction "VCC-DRAM8_59") (pintype "bidirectional"))
      (node (ref "U1") (pin "60") (pinfunction "VCC-DRAM9_60") (pintype "bidirectional"))
      (node (ref "U1") (pin "61") (pinfunction "VCC-DRAM10_61") (pintype "bidirectional"))
      (node (ref "U1") (pin "62") (pinfunction "VCC-DRAM11_62") (pintype "bidirectional"))
      (node (ref "U1") (pin "65") (pinfunction "VCC-DRAM0_65") (pintype "bidirectional"))
      (node (ref "U1") (pin "66") (pinfunction "VCC-DRAM1_66") (pintype "bidirectional"))
      (node (ref "U1") (pin "67") (pinfunction "VCC-DRAM2_67") (pintype "bidirectional"))
      (node (ref "U1") (pin "68") (pinfunction "VCC-DRAM3_68") (pintype "bidirectional"))
      (node (ref "U1") (pin "69") (pinfunction "VCC-DRAM4_69") (pintype "bidirectional"))
      (node (ref "U1") (pin "70") (pinfunction "VCC-DRAM5_70") (pintype "bidirectional"))
      (node (ref "U1") (pin "72") (pinfunction "VCC-DRAM6_72") (pintype "bidirectional"))
      (node (ref "U1") (pin "79") (pinfunction "VCC-DRAM7_79") (pintype "bidirectional"))
    )
    (net (code "3") (name "3V") (class "Default")
      (node (ref "C22") (pin "1") (pinfunction "1_1") (pintype "passive"))
      (node (ref "C23") (pin "1") (pinfunction "1_1") (pintype "passive"))
      (node (ref "U1") (pin "115") (pinfunction "AVCC_115") (pintype "bidirectional"))
      (node (ref "U1") (pin "76") (pinfunction "VCC-PLL_76") (pintype "bidirectional"))
      (node (ref "U5") (pin "2") (pinfunction "VOUT_2") (pintype "output"))
    )
    (net (code "4") (name "3V3") (class "Default")
      (node (ref "C20") (pin "1") (pinfunction "1_1") (pintype "passive"))
      (node (ref "C37") (pin "1") (pinfunction "1_1") (pintype "passive"))
      (node (ref "C38") (pin "1") (pinfunction "1_1") (pintype "passive"))
      (node (ref "C39") (pin "1") (pinfunction "1_1") (pintype "passive"))
      (node (ref "C40") (pin "2") (pinfunction "2_2") (pintype "passive"))
      (node (ref "C41") (pin "1") (pinfunction "1_1") (pintype "passive"))
      (node (ref "C42") (pin "1") (pinfunction "1_1") (pintype "passive"))
      (node (ref "C44") (pin "1") (pinfunction "1_1") (pintype "passive"))
      (node (ref "C45") (pin "1") (pinfunction "1_1") (pintype "passive"))
      (node (ref "C50") (pin "1") (pinfunction "1_1") (pintype "passive"))
      (node (ref "D1") (pin "1") (pinfunction "COMM_ANODE_1") (pintype "passive"))
      (node (ref "D2") (pin "1") (pinfunction "COMM_ANODE_1") (pintype "passive"))
      (node (ref "D3") (pin "1") (pinfunction "COMM_ANODE_1") (pintype "passive"))
      (node (ref "J3") (pin "4") (pinfunction "VDD_4") (pintype "power_in"))
      (node (ref "J4") (pin "2") (pinfunction "2_2") (pintype "bidirectional"))
      (node (ref "L4") (pin "1") (pinfunction "1_1") (pintype "passive"))
      (node (ref "P2") (pin "15") (pinfunction "15_15") (pintype "bidirectional"))
      (node (ref "R16") (pin "2") (pinfunction "2_2") (pintype "passive"))
      (node (ref "R20") (pin "1") (pinfunction "1_1") (pintype "passive"))
      (node (ref "R21") (pin "2") (pinfunction "2_2") (pintype "passive"))
      (node (ref "R22") (pin "2") (pinfunction "2_2") (pintype "passive"))
      (node (ref "R23") (pin "2") (pinfunction "2_2") (pintype "passive"))
      (node (ref "R24") (pin "2") (pinfunction "2_2") (pintype "passive"))
      (node (ref "R25") (pin "2") (pinfunction "2_2") (pintype "passive"))
      (node (ref "R26") (pin "2") (pinfunction "2_2") (pintype "passive"))
      (node (ref "R27") (pin "1") (pinfunction "1_1") (pintype "passive"))
      (node (ref "R28") (pin "1") (pinfunction "1_1") (pintype "passive"))
      (node (ref "R29") (pin "1") (pinfunction "1_1") (pintype "passive"))
      (node (ref "R30") (pin "1") (pinfunction "1_1") (pintype "passive"))
      (node (ref "R31") (pin "1") (pinfunction "1_1") (pintype "passive"))
      (node (ref "SJ1") (pin "2") (pinfunction "2_2") (pintype "passive"))
      (node (ref "SJ4") (pin "2") (pinfunction "2_2") (pintype "passive"))
      (node (ref "U1") (pin "104") (pinfunction "VCC-0_104") (pintype "bidirectional"))
      (node (ref "U1") (pin "109") (pinfunction "VCC-USB_109") (pintype "bidirectional"))
      (node (ref "U1") (pin "12") (pinfunction "VCC-PE0_12") (pintype "bidirectional"))
      (node (ref "U1") (pin "127") (pinfunction "VCC-1_127") (pintype "bidirectional"))
      (node (ref "U1") (pin "29") (pinfunction "VCC-PE1_29") (pintype "bidirectional"))
      (node (ref "U1") (pin "50") (pinfunction "VCC-3_50") (pintype "bidirectional"))
      (node (ref "U1") (pin "57") (pinfunction "VCC-2_57") (pintype "bidirectional"))
      (node (ref "U1") (pin "85") (pinfunction "VCC-MCSI_85") (pintype "bidirectional"))
      (node (ref "U1") (pin "93") (pinfunction "EPHY_VCC_93") (pintype "bidirectional"))
      (node (ref "U5") (pin "3") (pinfunction "VIN_3") (pintype "input"))
    )
    (net (code "5") (name "CAM_IO0") (class "Default")
      (node (ref "CAMIO0") (pin "1") (pinfunction "2_1") (pintype "passive"))
      (node (ref "P2") (pin "11") (pinfunction "11_11") (pintype "bidirectional"))
    )
    (net (code "6") (name "CAM_IO1") (class "Default")
      (node (ref "CAMIO1") (pin "1") (pinfunction "2_1") (pintype "passive"))
      (node (ref "P2") (pin "12") (pinfunction "12_12") (pintype "bidirectional"))
    )
    (net (code "7") (name "CK_N") (class "Default")
      (node (ref "P2") (pin "9") (pinfunction "9_9") (pintype "bidirectional"))
      (node (ref "U1") (pin "86") (pinfunction "MCSI-CKP_86") (pintype "bidirectional"))
    )
    (net (code "8") (name "CK_P") (class "Default")
      (node (ref "P2") (pin "8") (pinfunction "8_8") (pintype "bidirectional"))
      (node (ref "U1") (pin "87") (pinfunction "MCSI-CKN_87") (pintype "bidirectional"))
    )
    (net (code "9") (name "CS") (class "Default")
      (node (ref "CS") (pin "1") (pinfunction "2_1") (pintype "passive"))
      (node (ref "R31") (pin "2") (pinfunction "2_2") (pintype "passive"))
      (node (ref "U1") (pin "54") (pinfunction "PC2/SPI1/CS_54") (pintype "bidirectional"))
    )
    (net (code "10") (name "D0_N") (class "Default")
      (node (ref "P2") (pin "2") (pinfunction "2_2") (pintype "bidirectional"))
      (node (ref "U1") (pin "82") (pinfunction "MCSI-D0N_82") (pintype "bidirectional"))
    )
    (net (code "11") (name "D0_P") (class "Default")
      (node (ref "P2") (pin "3") (pinfunction "3_3") (pintype "bidirectional"))
      (node (ref "U1") (pin "81") (pinfunction "MCSI-D0P_81") (pintype "bidirectional"))
    )
    (net (code "12") (name "D1_N") (class "Default")
      (node (ref "P2") (pin "5") (pinfunction "5_5") (pintype "bidirectional"))
      (node (ref "U1") (pin "84") (pinfunction "MCSI-D1N_84") (pintype "bidirectional"))
    )
    (net (code "13") (name "D1_P") (class "Default")
      (node (ref "P2") (pin "6") (pinfunction "6_6") (pintype "bidirectional"))
      (node (ref "U1") (pin "83") (pinfunction "MCSI-D1P_83") (pintype "bidirectional"))
    )
    (net (code "14") (name "ETH_RX_N") (class "Default")
      (node (ref "J6") (pin "6") (pinfunction "RD-_6") (pintype "passive"))
      (node (ref "R34") (pin "1") (pinfunction "1_1") (pintype "passive"))
      (node (ref "U1") (pin "89") (pinfunction "EPHY_RXN_89") (pintype "bidirectional"))
    )
    (net (code "15") (name "ETH_RX_P") (class "Default")
      (node (ref "J6") (pin "3") (pinfunction "RD+_3") (pintype "passive"))
      (node (ref "R33") (pin "1") (pinfunction "1_1") (pintype "passive"))
      (node (ref "U1") (pin "90") (pinfunction "EPHY_RXP_90") (pintype "bidirectional"))
    )
    (net (code "16") (name "ETH_TX_N") (class "Default")
      (node (ref "J6") (pin "2") (pinfunction "TD-_2") (pintype "passive"))
      (node (ref "R39") (pin "1") (pinfunction "1_1") (pintype "passive"))
      (node (ref "U1") (pin "91") (pinfunction "EPHY_TXN_91") (pintype "bidirectional"))
    )
    (net (code "17") (name "ETH_TX_P") (class "Default")
      (node (ref "J6") (pin "1") (pinfunction "TD+_1") (pintype "passive"))
      (node (ref "R32") (pin "1") (pinfunction "1_1") (pintype "passive"))
      (node (ref "U1") (pin "92") (pinfunction "EPHY_TXP_92") (pintype "bidirectional"))
    )
    (net (code "18") (name "GND") (class "Default")
      (node (ref "C1") (pin "2") (pinfunction "2_2") (pintype "passive"))
      (node (ref "C11") (pin "2") (pinfunction "2_2") (pintype "passive"))
      (node (ref "C12") (pin "2") (pinfunction "-_2") (pintype "passive"))
      (node (ref "C13") (pin "2") (pinfunction "-_2") (pintype "passive"))
      (node (ref "C14") (pin "2") (pinfunction "2_2") (pintype "passive"))
      (node (ref "C16") (pin "2") (pinfunction "2_2") (pintype "passive"))
      (node (ref "C17") (pin "2") (pinfunction "-_2") (pintype "passive"))
      (node (ref "C18") (pin "2") (pinfunction "-_2") (pintype "passive"))
      (node (ref "C19") (pin "2") (pinfunction "2_2") (pintype "passive"))
      (node (ref "C2") (pin "2") (pinfunction "2_2") (pintype "passive"))
      (node (ref "C20") (pin "2") (pinfunction "2_2") (pintype "passive"))
      (node (ref "C21") (pin "2") (pinfunction "2_2") (pintype "passive"))
      (node (ref "C22") (pin "2") (pinfunction "2_2") (pintype "passive"))
      (node (ref "C23") (pin "2") (pinfunction "2_2") (pintype "passive"))
      (node (ref "C24") (pin "2") (pinfunction "2_2") (pintype "passive"))
      (node (ref "C25") (pin "2") (pinfunction "2_2") (pintype "passive"))
      (node (ref "C26") (pin "2") (pinfunction "2_2") (pintype "passive"))
      (node (ref "C27") (pin "2") (pinfunction "2_2") (pintype "passive"))
      (node (ref "C28") (pin "2") (pinfunction "2_2") (pintype "passive"))
      (node (ref "C29") (pin "2") (pinfunction "2_2") (pintype "passive"))
      (node (ref "C3") (pin "2") (pinfunction "2_2") (pintype "passive"))
      (node (ref "C30") (pin "2") (pinfunction "2_2") (pintype "passive"))
      (node (ref "C31") (pin "2") (pinfunction "2_2") (pintype "passive"))
      (node (ref "C32") (pin "2") (pinfunction "2_2") (pintype "passive"))
      (node (ref "C33") (pin "2") (pinfunction "2_2") (pintype "passive"))
      (node (ref "C34") (pin "2") (pinfunction "2_2") (pintype "passive"))
      (node (ref "C35") (pin "2") (pinfunction "2_2") (pintype "passive"))
      (node (ref "C36") (pin "2") (pinfunction "2_2") (pintype "passive"))
      (node (ref "C37") (pin "2") (pinfunction "2_2") (pintype "passive"))
      (node (ref "C38") (pin "2") (pinfunction "2_2") (pintype "passive"))
      (node (ref "C39") (pin "2") (pinfunction "2_2") (pintype "passive"))
      (node (ref "C4") (pin "2") (pinfunction "2_2") (pintype "passive"))
      (node (ref "C40") (pin "1") (pinfunction "1_1") (pintype "passive"))
      (node (ref "C41") (pin "2") (pinfunction "2_2") (pintype "passive"))
      (node (ref "C42") (pin "2") (pinfunction "2_2") (pintype "passive"))
      (node (ref "C44") (pin "2") (pinfunction "2_2") (pintype "passive"))
      (node (ref "C45") (pin "2") (pinfunction "2_2") (pintype "passive"))
      (node (ref "C46") (pin "1") (pinfunction "1_1") (pintype "passive"))
      (node (ref "C47") (pin "2") (pinfunction "2_2") (pintype "passive"))
      (node (ref "C48") (pin "2") (pinfunction "2_2") (pintype "passive"))
      (node (ref "C50") (pin "2") (pinfunction "2_2") (pintype "passive"))
      (node (ref "C54") (pin "1") (pinfunction "1_1") (pintype "passive"))
      (node (ref "C56") (pin "1") (pinfunction "1_1") (pintype "passive"))
      (node (ref "C57") (pin "2") (pinfunction "2_2") (pintype "passive"))
      (node (ref "C58") (pin "1") (pinfunction "1_1") (pintype "passive"))
      (node (ref "C6") (pin "2") (pinfunction "2_2") (pintype "passive"))
      (node (ref "C60") (pin "1") (pinfunction "1_1") (pintype "passive"))
      (node (ref "C61") (pin "2") (pinfunction "2_2") (pintype "passive"))
      (node (ref "C69") (pin "1") (pinfunction "1_1") (pintype "passive"))
      (node (ref "C7") (pin "2") (pinfunction "-_2") (pintype "passive"))
      (node (ref "C71") (pin "1") (pinfunction "1_1") (pintype "passive"))
      (node (ref "C72") (pin "2") (pinfunction "2_2") (pintype "passive"))
      (node (ref "C8") (pin "2") (pinfunction "-_2") (pintype "passive"))
      (node (ref "C9") (pin "2") (pinfunction "2_2") (pintype "passive"))
      (node (ref "GND") (pin "P$1") (pinfunction "1_P$1") (pintype "bidirectional"))
      (node (ref "IC2") (pin "2") (pinfunction "GND_2") (pintype "power_in"))
      (node (ref "IC5") (pin "2") (pinfunction "GND_2") (pintype "power_in"))
      (node (ref "IC6") (pin "2") (pinfunction "GND_2") (pintype "power_in"))
      (node (ref "J1") (pin "1") (pinfunction "1_1") (pintype "bidirectional"))
      (node (ref "J3") (pin "10") (pinfunction "GND_10") (pintype "power_in"))
      (node (ref "J3") (pin "13") (pinfunction "GND_13") (pintype "power_in"))
      (node (ref "J3") (pin "6") (pinfunction "VSS_6") (pintype "power_in"))
      (node (ref "J3") (pin "9") (pinfunction "GND_9") (pintype "power_in"))
      (node (ref "J4") (pin "1") (pinfunction "1_1") (pintype "bidirectional"))
      (node (ref "J5") (pin "1") (pinfunction "1_1") (pintype "bidirectional"))
      (node (ref "J6") (pin "10") (pinfunction "GC_10") (pintype "passive"))
      (node (ref "J6") (pin "11") (pinfunction "YC_11") (pintype "passive"))
      (node (ref "J6") (pin "15") (pinfunction "SHIELD_15") (pintype "passive"))
      (node (ref "J6") (pin "16") (pinfunction "SHIELD_16") (pintype "passive"))
      (node (ref "J6") (pin "8") (pinfunction "GND_8") (pintype "power_in"))
      (node (ref "P1") (pin "5") (pinfunction "GND_5") (pintype "bidirectional"))
      (node (ref "P1") (pin "SHELL") (pinfunction "SHIELD_SHELL") (pintype "bidirectional"))
      (node (ref "P1") (pin "SHELL1") (pinfunction "SHIELD_SHELL1") (pintype "bidirectional"))
      (node (ref "P1") (pin "SHELL2") (pinfunction "SHIELD_SHELL2") (pintype "bidirectional"))
      (node (ref "P1") (pin "SHELL3") (pinfunction "SHIELD_SHELL3") (pintype "bidirectional"))
      (node (ref "P2") (pin "1") (pinfunction "1_1") (pintype "bidirectional"))
      (node (ref "P2") (pin "10") (pinfunction "10_10") (pintype "bidirectional"))
      (node (ref "P2") (pin "4") (pinfunction "4_4") (pintype "bidirectional"))
      (node (ref "P2") (pin "7") (pinfunction "7_7") (pintype "bidirectional"))
      (node (ref "R11") (pin "2") (pinfunction "2_2") (pintype "passive"))
      (node (ref "R15") (pin "2") (pinfunction "2_2") (pintype "passive"))
      (node (ref "R3") (pin "1") (pinfunction "1_1") (pintype "passive"))
      (node (ref "R36") (pin "2") (pinfunction "2_2") (pintype "passive"))
      (node (ref "R38") (pin "2") (pinfunction "2_2") (pintype "passive"))
      (node (ref "R41") (pin "2") (pinfunction "2_2") (pintype "passive"))
      (node (ref "R42") (pin "1") (pinfunction "1_1") (pintype "passive"))
      (node (ref "R7") (pin "2") (pinfunction "2_2") (pintype "passive"))
      (node (ref "SW1") (pin "2") (pinfunction "S_2") (pintype "passive"))
      (node (ref "SW2") (pin "2") (pinfunction "S_2") (pintype "passive"))
      (node (ref "SW3") (pin "2") (pinfunction "S_2") (pintype "passive"))
      (node (ref "U1") (pin "116") (pinfunction "AGND_116") (pintype "bidirectional"))
      (node (ref "U1") (pin "P$1") (pinfunction "PAD_P$1") (pintype "bidirectional"))
      (node (ref "U2") (pin "2") (pinfunction "GND_2") (pintype "bidirectional"))
      (node (ref "U3") (pin "2") (pinfunction "GND_2") (pintype "bidirectional"))
      (node (ref "U4") (pin "2") (pinfunction "GND_2") (pintype "bidirectional"))
      (node (ref "U5") (pin "1") (pinfunction "VSS_1") (pintype "power_in"))
    )
    (net (code "19") (name "LED0") (class "Default")
      (node (ref "R18") (pin "1") (pinfunction "1_1") (pintype "passive"))
      (node (ref "U1") (pin "4") (pinfunction "PG1/SDC1/CMD_4") (pintype "bidirectional"))
    )
    (net (code "20") (name "LED1") (class "Default")
      (node (ref "R19") (pin "1") (pinfunction "1_1") (pintype "passive"))
      (node (ref "U1") (pin "5") (pinfunction "PG0/SDC1/CLK_5") (pintype "bidirectional"))
    )
    (net (code "21") (name "LED2") (class "Default")
      (node (ref "R17") (pin "1") (pinfunction "1_1") (pintype "passive"))
      (node (ref "U1") (pin "3") (pinfunction "PG2/SDC1/D0_3") (pintype "bidirectional"))
    )
    (net (code "22") (name "LED3") (class "Default")
      (node (ref "J6") (pin "9") (pinfunction "GA_9") (pintype "passive"))
      (node (ref "R1") (pin "1") (pinfunction "1_1") (pintype "passive"))
      (node (ref "U1") (pin "78") (pinfunction "EPHY_SPD_LED_78") (pintype "bidirectional"))
    )
    (net (code "23") (name "LED4") (class "Default")
      (node (ref "J6") (pin "12") (pinfunction "YA_12") (pintype "passive"))
      (node (ref "R2") (pin "1") (pinfunction "1_1") (pintype "passive"))
      (node (ref "U1") (pin "77") (pinfunction "EPHY_LINK_LED_77") (pintype "bidirectional"))
    )
    (net (code "24") (name "LEDD") (class "Default")
      (node (ref "J3") (pin "11") (pinfunction "DET_11") (pintype "passive"))
      (node (ref "R44") (pin "1") (pinfunction "1_1") (pintype "passive"))
    )
    (net (code "25") (name "LEDD0") (class "Default")
      (node (ref "J5") (pin "2") (pinfunction "2_2") (pintype "bidirectional"))
      (node (ref "PWM0") (pin "1") (pinfunction "2_1") (pintype "passive"))
      (node (ref "R45") (pin "1") (pinfunction "1_1") (pintype "passive"))
      (node (ref "U1") (pin "43") (pinfunction "PB4/PWM0_43") (pintype "bidirectional"))
    )
    (net (code "26") (name "LEDD1") (class "Default")
      (node (ref "PWM1") (pin "1") (pinfunction "2_1") (pintype "passive"))
      (node (ref "R46") (pin "1") (pinfunction "1_1") (pintype "passive"))
      (node (ref "U1") (pin "44") (pinfunction "PB5/PWM1_44") (pintype "bidirectional"))
    )
    (net (code "27") (name "MISO") (class "Default")
      (node (ref "MISO") (pin "1") (pinfunction "2_1") (pintype "passive"))
      (node (ref "U1") (pin "52") (pinfunction "PC0/SPI1/MISO_52") (pintype "bidirectional"))
    )
    (net (code "28") (name "MOSI") (class "Default")
      (node (ref "MOSI") (pin "1") (pinfunction "2_1") (pintype "passive"))
      (node (ref "U1") (pin "55") (pinfunction "PC3/SPI1/MOSI_55") (pintype "bidirectional"))
    )
    (net (code "29") (name "N$34") (class "Default")
      (node (ref "U1") (pin "97") (pinfunction "RTC-VIO_97") (pintype "bidirectional"))
    )
    (net (code "30") (name "N$42") (class "Default")
      (node (ref "U1") (pin "73") (pinfunction "SZQ_73") (pintype "bidirectional"))
    )
    (net (code "31") (name "N$43") (class "Default")
      (node (ref "U1") (pin "71") (pinfunction "SVREF0_71") (pintype "bidirectional"))
    )
    (net (code "32") (name "N$44") (class "Default")
      (node (ref "U1") (pin "63") (pinfunction "SVREF1_63") (pintype "bidirectional"))
    )
    (net (code "33") (name "Net-(D1-CATHODE_BLUE)") (class "Default")
      (node (ref "D1") (pin "4") (pinfunction "CATHODE_BLUE_4") (pintype "passive"))
      (node (ref "R3") (pin "2") (pinfunction "2_2") (pintype "passive"))
    )
    (net (code "34") (name "Net-(D1-CATHODE_GREEN)") (class "Default")
      (node (ref "D1") (pin "3") (pinfunction "CATHODE_GREEN_3") (pintype "passive"))
      (node (ref "R2") (pin "2") (pinfunction "2_2") (pintype "passive"))
    )
    (net (code "35") (name "Net-(D1-CATHODE_RED)") (class "Default")
      (node (ref "D1") (pin "2") (pinfunction "CATHODE_RED_2") (pintype "passive"))
      (node (ref "R1") (pin "2") (pinfunction "2_2") (pintype "passive"))
    )
    (net (code "36") (name "Net-(D2-CATHODE_BLUE)") (class "Default")
      (node (ref "D2") (pin "4") (pinfunction "CATHODE_BLUE_4") (pintype "passive"))
      (node (ref "R17") (pin "2") (pinfunction "2_2") (pintype "passive"))
    )
    (net (code "37") (name "Net-(D2-CATHODE_GREEN)") (class "Default")
      (node (ref "D2") (pin "3") (pinfunction "CATHODE_GREEN_3") (pintype "passive"))
      (node (ref "R18") (pin "2") (pinfunction "2_2") (pintype "passive"))
    )
    (net (code "38") (name "Net-(D2-CATHODE_RED)") (class "Default")
      (node (ref "D2") (pin "2") (pinfunction "CATHODE_RED_2") (pintype "passive"))
      (node (ref "R19") (pin "2") (pinfunction "2_2") (pintype "passive"))
    )
    (net (code "39") (name "Net-(D3-CATHODE_BLUE)") (class "Default")
      (node (ref "D3") (pin "4") (pinfunction "CATHODE_BLUE_4") (pintype "passive"))
      (node (ref "R44") (pin "2") (pinfunction "2_2") (pintype "passive"))
    )
    (net (code "40") (name "Net-(D3-CATHODE_GREEN)") (class "Default")
      (node (ref "D3") (pin "3") (pinfunction "CATHODE_GREEN_3") (pintype "passive"))
      (node (ref "R45") (pin "2") (pinfunction "2_2") (pintype "passive"))
    )
    (net (code "41") (name "Net-(D3-CATHODE_RED)") (class "Default")
      (node (ref "D3") (pin "2") (pinfunction "CATHODE_RED_2") (pintype "passive"))
      (node (ref "R46") (pin "2") (pinfunction "2_2") (pintype "passive"))
    )
    (net (code "42") (name "Net-(DIGITAL1-2)") (class "Default")
      (node (ref "DIGITAL1") (pin "1") (pinfunction "2_1") (pintype "passive"))
      (node (ref "SW3") (pin "1") (pinfunction "P_1") (pintype "passive"))
      (node (ref "U1") (pin "2") (pinfunction "PG3/SDC1/D1_2") (pintype "bidirectional"))
    )
    (net (code "43") (name "Net-(DIGITAL2-2)") (class "Default")
      (node (ref "DIGITAL2") (pin "1") (pinfunction "2_1") (pintype "passive"))
      (node (ref "SW1") (pin "1") (pinfunction "P_1") (pintype "passive"))
      (node (ref "U1") (pin "1") (pinfunction "PG4/SDC1/D2_1") (pintype "bidirectional"))
    )
    (net (code "44") (name "Net-(DIGITAL3-2)") (class "Default")
      (node (ref "DIGITAL3") (pin "1") (pinfunction "2_1") (pintype "passive"))
      (node (ref "U1") (pin "128") (pinfunction "PG5/SDC1/D3_128") (pintype "bidirectional"))
    )
    (net (code "45") (name "Net-(IC2-FB)") (class "Default")
      (node (ref "C70") (pin "1") (pinfunction "1_1") (pintype "passive"))
      (node (ref "IC2") (pin "5") (pinfunction "FB_5") (pintype "input"))
      (node (ref "R40") (pin "1") (pinfunction "1_1") (pintype "passive"))
      (node (ref "R41") (pin "1") (pinfunction "1_1") (pintype "passive"))
    )
    (net (code "46") (name "Net-(IC2-LX)") (class "Default")
      (node (ref "IC2") (pin "3") (pinfunction "LX_3") (pintype "bidirectional"))
      (node (ref "L7") (pin "P$1") (pinfunction "1_P$1") (pintype "passive"))
    )
    (net (code "47") (name "Net-(IC5-FB)") (class "Default")
      (node (ref "C55") (pin "1") (pinfunction "1_1") (pintype "passive"))
      (node (ref "IC5") (pin "5") (pinfunction "FB_5") (pintype "input"))
      (node (ref "R35") (pin "1") (pinfunction "1_1") (pintype "passive"))
      (node (ref "R36") (pin "1") (pinfunction "1_1") (pintype "passive"))
    )
    (net (code "48") (name "Net-(IC5-LX)") (class "Default")
      (node (ref "IC5") (pin "3") (pinfunction "LX_3") (pintype "bidirectional"))
      (node (ref "L6") (pin "P$1") (pinfunction "1_P$1") (pintype "passive"))
    )
    (net (code "49") (name "Net-(IC6-FB)") (class "Default")
      (node (ref "C59") (pin "1") (pinfunction "1_1") (pintype "passive"))
      (node (ref "IC6") (pin "5") (pinfunction "FB_5") (pintype "input"))
      (node (ref "R37") (pin "1") (pinfunction "1_1") (pintype "passive"))
      (node (ref "R38") (pin "1") (pinfunction "1_1") (pintype "passive"))
    )
    (net (code "50") (name "Net-(IC6-LX)") (class "Default")
      (node (ref "IC6") (pin "3") (pinfunction "LX_3") (pintype "bidirectional"))
      (node (ref "L9") (pin "P$1") (pinfunction "1_P$1") (pintype "passive"))
    )
    (net (code "51") (name "Net-(J6-P4)") (class "Default")
      (node (ref "C47") (pin "1") (pinfunction "1_1") (pintype "passive"))
      (node (ref "J6") (pin "4") (pinfunction "P4_4") (pintype "passive"))
      (node (ref "R32") (pin "2") (pinfunction "2_2") (pintype "passive"))
      (node (ref "R39") (pin "2") (pinfunction "2_2") (pintype "passive"))
    )
    (net (code "52") (name "Net-(J6-P5)") (class "Default")
      (node (ref "C48") (pin "1") (pinfunction "1_1") (pintype "passive"))
      (node (ref "J6") (pin "5") (pinfunction "P5_5") (pintype "passive"))
      (node (ref "L4") (pin "2") (pinfunction "2_2") (pintype "passive"))
      (node (ref "R33") (pin "2") (pinfunction "2_2") (pintype "passive"))
      (node (ref "R34") (pin "2") (pinfunction "2_2") (pintype "passive"))
    )
    (net (code "53") (name "Net-(L1-1)") (class "Default")
      (node (ref "C5") (pin "2") (pinfunction "2_2") (pintype "passive"))
      (node (ref "L1") (pin "P$1") (pinfunction "1_P$1") (pintype "passive"))
      (node (ref "U2") (pin "3") (pinfunction "SW_3") (pintype "bidirectional"))
    )
    (net (code "54") (name "Net-(L2-1)") (class "Default")
      (node (ref "C10") (pin "2") (pinfunction "2_2") (pintype "passive"))
      (node (ref "L2") (pin "P$1") (pinfunction "1_P$1") (pintype "passive"))
      (node (ref "U3") (pin "3") (pinfunction "SW_3") (pintype "bidirectional"))
    )
    (net (code "55") (name "Net-(L3-1)") (class "Default")
      (node (ref "C15") (pin "2") (pinfunction "2_2") (pintype "passive"))
      (node (ref "L3") (pin "P$1") (pinfunction "1_P$1") (pintype "passive"))
      (node (ref "U4") (pin "3") (pinfunction "SW_3") (pintype "bidirectional"))
    )
    (net (code "56") (name "Net-(PB2-2)") (class "Default")
      (node (ref "PB2") (pin "1") (pinfunction "2_1") (pintype "passive"))
      (node (ref "SW2") (pin "1") (pinfunction "P_1") (pintype "passive"))
      (node (ref "U1") (pin "41") (pinfunction "PB2_41") (pintype "bidirectional"))
    )
    (net (code "57") (name "Net-(PB3-2)") (class "Default")
      (node (ref "PB3") (pin "1") (pinfunction "2_1") (pintype "passive"))
      (node (ref "U1") (pin "42") (pinfunction "PB3_42") (pintype "bidirectional"))
    )
    (net (code "58") (name "Net-(R5-Pad1)") (class "Default")
      (node (ref "R5") (pin "1") (pinfunction "1_1") (pintype "passive"))
      (node (ref "R6") (pin "2") (pinfunction "2_2") (pintype "passive"))
      (node (ref "R7") (pin "1") (pinfunction "1_1") (pintype "passive"))
    )
    (net (code "59") (name "Net-(R10-Pad2)") (class "Default")
      (node (ref "R10") (pin "2") (pinfunction "2_2") (pintype "passive"))
      (node (ref "R11") (pin "1") (pinfunction "1_1") (pintype "passive"))
      (node (ref "R9") (pin "1") (pinfunction "1_1") (pintype "passive"))
    )
    (net (code "60") (name "Net-(R13-Pad1)") (class "Default")
      (node (ref "R13") (pin "1") (pinfunction "1_1") (pintype "passive"))
      (node (ref "R14") (pin "2") (pinfunction "2_2") (pintype "passive"))
      (node (ref "R15") (pin "1") (pinfunction "1_1") (pintype "passive"))
    )
    (net (code "61") (name "Net-(RX1-2)") (class "Default")
      (node (ref "RX1") (pin "1") (pinfunction "2_1") (pintype "passive"))
      (node (ref "U1") (pin "8") (pinfunction "PE22/UART1/RX_8") (pintype "bidirectional"))
    )
    (net (code "62") (name "Net-(RX2-2)") (class "Default")
      (node (ref "RX2") (pin "1") (pinfunction "2_1") (pintype "passive"))
      (node (ref "U1") (pin "40") (pinfunction "PB1/UART2/RX_40") (pintype "bidirectional"))
    )
    (net (code "63") (name "Net-(TX1-2)") (class "Default")
      (node (ref "TX1") (pin "1") (pinfunction "2_1") (pintype "passive"))
      (node (ref "U1") (pin "9") (pinfunction "PE21/UART1/TX_9") (pintype "bidirectional"))
    )
    (net (code "64") (name "Net-(TX2-2)") (class "Default")
      (node (ref "TX2") (pin "1") (pinfunction "2_1") (pintype "passive"))
      (node (ref "U1") (pin "39") (pinfunction "PB0/UART2/TX_39") (pintype "bidirectional"))
    )
    (net (code "65") (name "Net-(U1D-X24MIN)") (class "Default")
      (node (ref "C4") (pin "1") (pinfunction "1_1") (pintype "passive"))
      (node (ref "U1") (pin "75") (pinfunction "X24MIN_75") (pintype "bidirectional"))
      (node (ref "X1") (pin "P$3") (pinfunction "2_P$3") (pintype "passive"))
    )
    (net (code "66") (name "Net-(U1D-X24MOUNT)") (class "Default")
      (node (ref "C3") (pin "1") (pinfunction "1_1") (pintype "passive"))
      (node (ref "U1") (pin "74") (pinfunction "X24MOUNT_74") (pintype "bidirectional"))
      (node (ref "X1") (pin "P$1") (pinfunction "1_P$1") (pintype "passive"))
    )
    (net (code "67") (name "Net-(U1D-X32KIN)") (class "Default")
      (node (ref "C2") (pin "1") (pinfunction "1_1") (pintype "passive"))
      (node (ref "U1") (pin "96") (pinfunction "X32KIN_96") (pintype "bidirectional"))
      (node (ref "X2") (pin "P$1") (pinfunction "1_P$1") (pintype "passive"))
    )
    (net (code "68") (name "Net-(U1D-X32KOUT)") (class "Default")
      (node (ref "C1") (pin "1") (pinfunction "1_1") (pintype "passive"))
      (node (ref "U1") (pin "95") (pinfunction "X32KOUT_95") (pintype "bidirectional"))
      (node (ref "X2") (pin "P$2") (pinfunction "2_P$2") (pintype "passive"))
    )
    (net (code "69") (name "Net-(U1E-EPHY_RTX)") (class "Default")
      (node (ref "R42") (pin "2") (pinfunction "2_2") (pintype "passive"))
      (node (ref "U1") (pin "94") (pinfunction "EPHY_RTX_94") (pintype "bidirectional"))
    )
    (net (code "70") (name "Net-(U1F-VCC-RTC)") (class "Default")
      (node (ref "R16") (pin "1") (pinfunction "1_1") (pintype "passive"))
      (node (ref "U1") (pin "98") (pinfunction "VCC-RTC_98") (pintype "bidirectional"))
    )
    (net (code "71") (name "Net-(U2-BST)") (class "Default")
      (node (ref "C5") (pin "1") (pinfunction "1_1") (pintype "passive"))
      (node (ref "U2") (pin "4") (pinfunction "BST_4") (pintype "bidirectional"))
    )
    (net (code "72") (name "Net-(U2-ENABLE)") (class "Default")
      (node (ref "R4") (pin "1") (pinfunction "1_1") (pintype "passive"))
      (node (ref "U2") (pin "5") (pinfunction "ENABLE_5") (pintype "bidirectional"))
    )
    (net (code "73") (name "Net-(U2-FB)") (class "Default")
      (node (ref "R5") (pin "2") (pinfunction "2_2") (pintype "passive"))
      (node (ref "U2") (pin "6") (pinfunction "FB_6") (pintype "bidirectional"))
    )
    (net (code "74") (name "Net-(U3-BST)") (class "Default")
      (node (ref "C10") (pin "1") (pinfunction "1_1") (pintype "passive"))
      (node (ref "U3") (pin "4") (pinfunction "BST_4") (pintype "bidirectional"))
    )
    (net (code "75") (name "Net-(U3-ENABLE)") (class "Default")
      (node (ref "R8") (pin "1") (pinfunction "1_1") (pintype "passive"))
      (node (ref "U3") (pin "5") (pinfunction "ENABLE_5") (pintype "bidirectional"))
    )
    (net (code "76") (name "Net-(U3-FB)") (class "Default")
      (node (ref "R9") (pin "2") (pinfunction "2_2") (pintype "passive"))
      (node (ref "U3") (pin "6") (pinfunction "FB_6") (pintype "bidirectional"))
    )
    (net (code "77") (name "Net-(U4-BST)") (class "Default")
      (node (ref "C15") (pin "1") (pinfunction "1_1") (pintype "passive"))
      (node (ref "U4") (pin "4") (pinfunction "BST_4") (pintype "bidirectional"))
    )
    (net (code "78") (name "Net-(U4-ENABLE)") (class "Default")
      (node (ref "R12") (pin "1") (pinfunction "1_1") (pintype "passive"))
      (node (ref "U4") (pin "5") (pinfunction "ENABLE_5") (pintype "bidirectional"))
    )
    (net (code "79") (name "Net-(U4-FB)") (class "Default")
      (node (ref "R13") (pin "2") (pinfunction "2_2") (pintype "passive"))
      (node (ref "U4") (pin "6") (pinfunction "FB_6") (pintype "bidirectional"))
    )
    (net (code "80") (name "P1V2") (class "Default")
      (node (ref "C18") (pin "1") (pinfunction "+_1") (pintype "passive"))
      (node (ref "C19") (pin "1") (pinfunction "1_1") (pintype "passive"))
      (node (ref "L3") (pin "P$2") (pinfunction "2_P$2") (pintype "passive"))
      (node (ref "R14") (pin "1") (pinfunction "1_1") (pintype "passive"))
      (node (ref "SJ6") (pin "1") (pinfunction "1_1") (pintype "passive"))
    )
    (net (code "81") (name "P1V8") (class "Default")
      (node (ref "C13") (pin "1") (pinfunction "+_1") (pintype "passive"))
      (node (ref "C14") (pin "1") (pinfunction "1_1") (pintype "passive"))
      (node (ref "L2") (pin "P$2") (pinfunction "2_P$2") (pintype "passive"))
      (node (ref "R10") (pin "1") (pinfunction "1_1") (pintype "passive"))
      (node (ref "SJ5") (pin "1") (pinfunction "1_1") (pintype "passive"))
    )
    (net (code "82") (name "P3V3") (class "Default")
      (node (ref "C8") (pin "1") (pinfunction "+_1") (pintype "passive"))
      (node (ref "C9") (pin "1") (pinfunction "1_1") (pintype "passive"))
      (node (ref "L1") (pin "P$2") (pinfunction "2_P$2") (pintype "passive"))
      (node (ref "R6") (pin "1") (pinfunction "1_1") (pintype "passive"))
      (node (ref "SJ4") (pin "1") (pinfunction "1_1") (pintype "passive"))
    )
    (net (code "83") (name "PRE1V2") (class "Default")
      (node (ref "C54") (pin "2") (pinfunction "2_2") (pintype "passive"))
      (node (ref "C55") (pin "2") (pinfunction "2_2") (pintype "passive"))
      (node (ref "C56") (pin "2") (pinfunction "2_2") (pintype "passive"))
      (node (ref "L6") (pin "P$2") (pinfunction "2_P$2") (pintype "passive"))
      (node (ref "R35") (pin "2") (pinfunction "2_2") (pintype "passive"))
      (node (ref "SJ8") (pin "1") (pinfunction "1_1") (pintype "passive"))
    )
    (net (code "84") (name "PRE1V8") (class "Default")
      (node (ref "C58") (pin "2") (pinfunction "2_2") (pintype "passive"))
      (node (ref "C59") (pin "2") (pinfunction "2_2") (pintype "passive"))
      (node (ref "C60") (pin "2") (pinfunction "2_2") (pintype "passive"))
      (node (ref "L9") (pin "P$2") (pinfunction "2_P$2") (pintype "passive"))
      (node (ref "R37") (pin "2") (pinfunction "2_2") (pintype "passive"))
      (node (ref "SJ9") (pin "1") (pinfunction "1_1") (pintype "passive"))
    )
    (net (code "85") (name "PRE3V3") (class "Default")
      (node (ref "C69") (pin "2") (pinfunction "2_2") (pintype "passive"))
      (node (ref "C70") (pin "2") (pinfunction "2_2") (pintype "passive"))
      (node (ref "C71") (pin "2") (pinfunction "2_2") (pintype "passive"))
      (node (ref "L7") (pin "P$2") (pinfunction "2_P$2") (pintype "passive"))
      (node (ref "R40") (pin "2") (pinfunction "2_2") (pintype "passive"))
      (node (ref "SJ1") (pin "1") (pinfunction "1_1") (pintype "passive"))
    )
    (net (code "86") (name "RX0") (class "Default")
      (node (ref "J1") (pin "2") (pinfunction "2_2") (pintype "bidirectional"))
      (node (ref "R29") (pin "2") (pinfunction "2_2") (pintype "passive"))
      (node (ref "U1") (pin "48") (pinfunction "PB8/I2C1/SCL_48") (pintype "bidirectional"))
    )
    (net (code "87") (name "SCK") (class "Default")
      (node (ref "SCK") (pin "1") (pinfunction "2_1") (pintype "passive"))
      (node (ref "U1") (pin "53") (pinfunction "PC1/SPI1/SCK_53") (pintype "bidirectional"))
    )
    (net (code "88") (name "SCL") (class "Default")
      (node (ref "J4") (pin "3") (pinfunction "3_3") (pintype "bidirectional"))
      (node (ref "P2") (pin "13") (pinfunction "13_13") (pintype "bidirectional"))
      (node (ref "R27") (pin "2") (pinfunction "2_2") (pintype "passive"))
      (node (ref "SCL0") (pin "1") (pinfunction "2_1") (pintype "passive"))
      (node (ref "U1") (pin "45") (pinfunction "PB6/I2C0/SCL_45") (pintype "bidirectional"))
    )
    (net (code "89") (name "SDA") (class "Default")
      (node (ref "J4") (pin "4") (pinfunction "4_4") (pintype "bidirectional"))
      (node (ref "P2") (pin "14") (pinfunction "14_14") (pintype "bidirectional"))
      (node (ref "R28") (pin "2") (pinfunction "2_2") (pintype "passive"))
      (node (ref "SDA0") (pin "1") (pinfunction "2_1") (pintype "passive"))
      (node (ref "U1") (pin "46") (pinfunction "PB7/I2C0/SDA_46") (pintype "bidirectional"))
    )
    (net (code "90") (name "SDC0_CLK") (class "Default")
      (node (ref "J3") (pin "5") (pinfunction "CLK_5") (pintype "bidirectional"))
      (node (ref "R26") (pin "1") (pinfunction "1_1") (pintype "passive"))
      (node (ref "U1") (pin "105") (pinfunction "PF2/SDC0/CLK_105") (pintype "bidirectional"))
    )
    (net (code "91") (name "SDC0_CMD") (class "Default")
      (node (ref "J3") (pin "3") (pinfunction "CMD_3") (pintype "bidirectional"))
      (node (ref "R25") (pin "1") (pinfunction "1_1") (pintype "passive"))
      (node (ref "U1") (pin "103") (pinfunction "PF3/SDC0/CMD_103") (pintype "bidirectional"))
    )
    (net (code "92") (name "SDC0_D0") (class "Default")
      (node (ref "J3") (pin "7") (pinfunction "DAT0_7") (pintype "bidirectional"))
      (node (ref "R21") (pin "1") (pinfunction "1_1") (pintype "passive"))
      (node (ref "U1") (pin "106") (pinfunction "PF1/SDC0/D0_106") (pintype "bidirectional"))
    )
    (net (code "93") (name "SDC0_D1") (class "Default")
      (node (ref "J3") (pin "8") (pinfunction "DAT1_8") (pintype "bidirectional"))
      (node (ref "R22") (pin "1") (pinfunction "1_1") (pintype "passive"))
      (node (ref "U1") (pin "107") (pinfunction "PF0/SDC0/D1_107") (pintype "bidirectional"))
    )
    (net (code "94") (name "SDC0_D2") (class "Default")
      (node (ref "J3") (pin "1") (pinfunction "DAT2_1") (pintype "bidirectional"))
      (node (ref "R23") (pin "1") (pinfunction "1_1") (pintype "passive"))
      (node (ref "U1") (pin "101") (pinfunction "PF5/SDC0/D2_101") (pintype "bidirectional"))
    )
    (net (code "95") (name "SDC0_D3") (class "Default")
      (node (ref "J3") (pin "2") (pinfunction "DAT3/CD_2") (pintype "bidirectional"))
      (node (ref "R24") (pin "1") (pinfunction "1_1") (pintype "passive"))
      (node (ref "U1") (pin "102") (pinfunction "PF4/SDC0/D3_102") (pintype "bidirectional"))
    )
    (net (code "96") (name "TX0") (class "Default")
      (node (ref "J1") (pin "3") (pinfunction "3_3") (pintype "bidirectional"))
      (node (ref "R30") (pin "2") (pinfunction "2_2") (pintype "passive"))
      (node (ref "U1") (pin "49") (pinfunction "PB9/I2C1/SDA_49") (pintype "bidirectional"))
    )
    (net (code "97") (name "USBDIFF_N") (class "Default")
      (node (ref "P1") (pin "2") (pinfunction "D-_2") (pintype "bidirectional"))
      (node (ref "U1") (pin "110") (pinfunction "USB-DM_110") (pintype "bidirectional"))
    )
    (net (code "98") (name "USBDIFF_P") (class "Default")
      (node (ref "P1") (pin "3") (pinfunction "D+_3") (pintype "bidirectional"))
      (node (ref "U1") (pin "111") (pinfunction "USB-DP_111") (pintype "bidirectional"))
    )
    (net (code "99") (name "USB_ID") (class "Default")
      (node (ref "P1") (pin "4") (pinfunction "ID_4") (pintype "bidirectional"))
      (node (ref "R20") (pin "2") (pinfunction "2_2") (pintype "passive"))
      (node (ref "U1") (pin "100") (pinfunction "PF6_100") (pintype "bidirectional"))
    )
    (net (code "100") (name "VCC") (class "Default")
      (node (ref "5V") (pin "P$1") (pinfunction "1_P$1") (pintype "bidirectional"))
      (node (ref "C11") (pin "1") (pinfunction "1_1") (pintype "passive"))
      (node (ref "C12") (pin "1") (pinfunction "+_1") (pintype "passive"))
      (node (ref "C16") (pin "1") (pinfunction "1_1") (pintype "passive"))
      (node (ref "C17") (pin "1") (pinfunction "+_1") (pintype "passive"))
      (node (ref "C21") (pin "1") (pinfunction "1_1") (pintype "passive"))
      (node (ref "C46") (pin "2") (pinfunction "2_2") (pintype "passive"))
      (node (ref "C57") (pin "1") (pinfunction "1_1") (pintype "passive"))
      (node (ref "C6") (pin "1") (pinfunction "1_1") (pintype "passive"))
      (node (ref "C61") (pin "1") (pinfunction "1_1") (pintype "passive"))
      (node (ref "C7") (pin "1") (pinfunction "+_1") (pintype "passive"))
      (node (ref "C72") (pin "1") (pinfunction "1_1") (pintype "passive"))
      (node (ref "IC2") (pin "1") (pinfunction "EN_1") (pintype "input"))
      (node (ref "IC2") (pin "4") (pinfunction "VIN_4") (pintype "power_in"))
      (node (ref "IC5") (pin "1") (pinfunction "EN_1") (pintype "input"))
      (node (ref "IC5") (pin "4") (pinfunction "VIN_4") (pintype "power_in"))
      (node (ref "IC6") (pin "1") (pinfunction "EN_1") (pintype "input"))
      (node (ref "IC6") (pin "4") (pinfunction "VIN_4") (pintype "power_in"))
      (node (ref "J5") (pin "3") (pinfunction "3_3") (pintype "bidirectional"))
      (node (ref "P1") (pin "1") (pinfunction "VBUS_1") (pintype "bidirectional"))
      (node (ref "R12") (pin "2") (pinfunction "2_2") (pintype "passive"))
      (node (ref "R4") (pin "2") (pinfunction "2_2") (pintype "passive"))
      (node (ref "R8") (pin "2") (pinfunction "2_2") (pintype "passive"))
      (node (ref "U2") (pin "1") (pinfunction "VIN_1") (pintype "bidirectional"))
      (node (ref "U3") (pin "1") (pinfunction "VIN_1") (pintype "bidirectional"))
      (node (ref "U4") (pin "1") (pinfunction "VIN_1") (pintype "bidirectional"))
    )
    (net (code "101") (name "unconnected-(J3-POL-Pad12)") (class "Default")
      (node (ref "J3") (pin "12") (pinfunction "POL_12") (pintype "passive"))
    )
    (net (code "102") (name "unconnected-(SW1-P1-Pad3)") (class "Default")
      (node (ref "SW1") (pin "3") (pinfunction "P1_3") (pintype "passive"))
    )
    (net (code "103") (name "unconnected-(SW1-S1-Pad4)") (class "Default")
      (node (ref "SW1") (pin "4") (pinfunction "S1_4") (pintype "passive"))
    )
    (net (code "104") (name "unconnected-(SW2-P1-Pad3)") (class "Default")
      (node (ref "SW2") (pin "3") (pinfunction "P1_3") (pintype "passive"))
    )
    (net (code "105") (name "unconnected-(SW2-S1-Pad4)") (class "Default")
      (node (ref "SW2") (pin "4") (pinfunction "S1_4") (pintype "passive"))
    )
    (net (code "106") (name "unconnected-(SW3-P1-Pad3)") (class "Default")
      (node (ref "SW3") (pin "3") (pinfunction "P1_3") (pintype "passive"))
    )
    (net (code "107") (name "unconnected-(SW3-S1-Pad4)") (class "Default")
      (node (ref "SW3") (pin "4") (pinfunction "S1_4") (pintype "passive"))
    )
    (net (code "108") (name "unconnected-(U1A-HBIAS-Pad119)") (class "Default")
      (node (ref "U1") (pin "119") (pinfunction "HBIAS_119") (pintype "bidirectional"))
    )
    (net (code "109") (name "unconnected-(U1A-HPCOM-Pad125)") (class "Default")
      (node (ref "U1") (pin "125") (pinfunction "HPCOM_125") (pintype "bidirectional"))
    )
    (net (code "110") (name "unconnected-(U1A-HPCOMFB-Pad124)") (class "Default")
      (node (ref "U1") (pin "124") (pinfunction "HPCOMFB_124") (pintype "bidirectional"))
    )
    (net (code "111") (name "unconnected-(U1A-HPOUTL-Pad121)") (class "Default")
      (node (ref "U1") (pin "121") (pinfunction "HPOUTL_121") (pintype "bidirectional"))
    )
    (net (code "112") (name "unconnected-(U1A-HPOUTR-Pad120)") (class "Default")
      (node (ref "U1") (pin "120") (pinfunction "HPOUTR_120") (pintype "bidirectional"))
    )
    (net (code "113") (name "unconnected-(U1A-HPVCCBP-Pad123)") (class "Default")
      (node (ref "U1") (pin "123") (pinfunction "HPVCCBP_123") (pintype "bidirectional"))
    )
    (net (code "114") (name "unconnected-(U1A-HPVCCIN-Pad122)") (class "Default")
      (node (ref "U1") (pin "122") (pinfunction "HPVCCIN_122") (pintype "bidirectional"))
    )
    (net (code "115") (name "unconnected-(U1A-MICIN1N-Pad114)") (class "Default")
      (node (ref "U1") (pin "114") (pinfunction "MICIN1N_114") (pintype "bidirectional"))
    )
    (net (code "116") (name "unconnected-(U1A-MICIN1P-Pad113)") (class "Default")
      (node (ref "U1") (pin "113") (pinfunction "MICIN1P_113") (pintype "bidirectional"))
    )
    (net (code "117") (name "unconnected-(U1A-VRA1-Pad117)") (class "Default")
      (node (ref "U1") (pin "117") (pinfunction "VRA1_117") (pintype "bidirectional"))
    )
    (net (code "118") (name "unconnected-(U1A-VRA2-Pad118)") (class "Default")
      (node (ref "U1") (pin "118") (pinfunction "VRA2_118") (pintype "bidirectional"))
    )
    (net (code "119") (name "unconnected-(U1B-LRADC0-Pad112)") (class "Default")
      (node (ref "U1") (pin "112") (pinfunction "LRADC0_112") (pintype "bidirectional"))
    )
    (net (code "120") (name "unconnected-(U1B-PE0{slash}CSI-CLK-{slash}LCD-CLK-Pad37)") (class "Default")
      (node (ref "U1") (pin "37") (pinfunction "PE0/CSI-CLK-/LCD-CLK_37") (pintype "bidirectional"))
    )
    (net (code "121") (name "unconnected-(U1B-PE1{slash}CSI-MCLK{slash}LCD-DE-Pad36)") (class "Default")
      (node (ref "U1") (pin "36") (pinfunction "PE1/CSI-MCLK/LCD-DE_36") (pintype "bidirectional"))
    )
    (net (code "122") (name "unconnected-(U1B-PE2{slash}CSI-HSYNC{slash}LCD-HSYNC-Pad35)") (class "Default")
      (node (ref "U1") (pin "35") (pinfunction "PE2/CSI-HSYNC/LCD-HSYNC_35") (pintype "bidirectional"))
    )
    (net (code "123") (name "unconnected-(U1B-PE3{slash}CSI-VSYNC{slash}LCD-VSYNC-Pad34)") (class "Default")
      (node (ref "U1") (pin "34") (pinfunction "PE3/CSI-VSYNC/LCD-VSYNC_34") (pintype "bidirectional"))
    )
    (net (code "124") (name "unconnected-(U1B-PE4{slash}CSI-D0{slash}LCD-D2-Pad33)") (class "Default")
      (node (ref "U1") (pin "33") (pinfunction "PE4/CSI-D0/LCD-D2_33") (pintype "bidirectional"))
    )
    (net (code "125") (name "unconnected-(U1B-PE5{slash}CSI-D1{slash}-LCD-D3-Pad32)") (class "Default")
      (node (ref "U1") (pin "32") (pinfunction "PE5/CSI-D1/-LCD-D3_32") (pintype "bidirectional"))
    )
    (net (code "126") (name "unconnected-(U1B-PE6{slash}CSI-D2{slash}LCD-D4-Pad31)") (class "Default")
      (node (ref "U1") (pin "31") (pinfunction "PE6/CSI-D2/LCD-D4_31") (pintype "bidirectional"))
    )
    (net (code "127") (name "unconnected-(U1B-PE7{slash}CSI-D3{slash}LCD-D5-Pad30)") (class "Default")
      (node (ref "U1") (pin "30") (pinfunction "PE7/CSI-D3/LCD-D5_30") (pintype "bidirectional"))
    )
    (net (code "128") (name "unconnected-(U1B-PE8{slash}CSI-D4{slash}LCD-D6-Pad28)") (class "Default")
      (node (ref "U1") (pin "28") (pinfunction "PE8/CSI-D4/LCD-D6_28") (pintype "bidirectional"))
    )
    (net (code "129") (name "unconnected-(U1B-PE9{slash}CSI-D5{slash}LCD-D7-Pad27)") (class "Default")
      (node (ref "U1") (pin "27") (pinfunction "PE9/CSI-D5/LCD-D7_27") (pintype "bidirectional"))
    )
    (net (code "130") (name "unconnected-(U1B-PE10{slash}CSI-D6{slash}LCD-D10-Pad24)") (class "Default")
      (node (ref "U1") (pin "24") (pinfunction "PE10/CSI-D6/LCD-D10_24") (pintype "bidirectional"))
    )
    (net (code "131") (name "unconnected-(U1B-PE11{slash}CSI-D7{slash}LCD-D11-Pad23)") (class "Default")
      (node (ref "U1") (pin "23") (pinfunction "PE11/CSI-D7/LCD-D11_23") (pintype "bidirectional"))
    )
    (net (code "132") (name "unconnected-(U1B-PE12{slash}CSI-D8{slash}LCD-D12-Pad22)") (class "Default")
      (node (ref "U1") (pin "22") (pinfunction "PE12/CSI-D8/LCD-D12_22") (pintype "bidirectional"))
    )
    (net (code "133") (name "unconnected-(U1B-PE13{slash}CSI-D9{slash}LCD-D13-Pad18)") (class "Default")
      (node (ref "U1") (pin "18") (pinfunction "PE13/CSI-D9/LCD-D13_18") (pintype "bidirectional"))
    )
    (net (code "134") (name "unconnected-(U1B-PE14{slash}CSI-D10{slash}LCD-D14-Pad17)") (class "Default")
      (node (ref "U1") (pin "17") (pinfunction "PE14/CSI-D10/LCD-D14_17") (pintype "bidirectional"))
    )
    (net (code "135") (name "unconnected-(U1B-PE15{slash}CSI-D11{slash}LCD-D15-Pad16)") (class "Default")
      (node (ref "U1") (pin "16") (pinfunction "PE15/CSI-D11/LCD-D15_16") (pintype "bidirectional"))
    )
    (net (code "136") (name "unconnected-(U1B-PE16{slash}CSI-D12{slash}LCD-D18-Pad15)") (class "Default")
      (node (ref "U1") (pin "15") (pinfunction "PE16/CSI-D12/LCD-D18_15") (pintype "bidirectional"))
    )
    (net (code "137") (name "unconnected-(U1B-PE17{slash}CSI-D13{slash}LCD-D19-Pad14)") (class "Default")
      (node (ref "U1") (pin "14") (pinfunction "PE17/CSI-D13/LCD-D19_14") (pintype "bidirectional"))
    )
    (net (code "138") (name "unconnected-(U1B-PE18{slash}CSI-D14{slash}LCD-D20-Pad13)") (class "Default")
      (node (ref "U1") (pin "13") (pinfunction "PE18/CSI-D14/LCD-D20_13") (pintype "bidirectional"))
    )
    (net (code "139") (name "unconnected-(U1B-PE19{slash}CSI-D15{slash}LCD-D21-Pad11)") (class "Default")
      (node (ref "U1") (pin "11") (pinfunction "PE19/CSI-D15/LCD-D21_11") (pintype "bidirectional"))
    )
    (net (code "140") (name "unconnected-(U1B-PE20{slash}CSI-FIELD{slash}CSI-MIPI-M-CLK-Pad10)") (class "Default")
      (node (ref "U1") (pin "10") (pinfunction "PE20/CSI-FIELD/CSI-MIPI-M-CLK_10") (pintype "bidirectional"))
    )
    (net (code "141") (name "unconnected-(U1B-PE23{slash}LCD-D22{slash}-Pad7)") (class "Default")
      (node (ref "U1") (pin "7") (pinfunction "PE23/LCD-D22/_7") (pintype "bidirectional"))
    )
    (net (code "142") (name "unconnected-(U1B-PE24{slash}LCD-D23-Pad6)") (class "Default")
      (node (ref "U1") (pin "6") (pinfunction "PE24/LCD-D23_6") (pintype "bidirectional"))
    )
    (net (code "143") (name "unconnected-(U1D-RESET-Pad99)") (class "Default")
      (node (ref "U1") (pin "99") (pinfunction "RESET_99") (pintype "bidirectional"))
    )
  )
)
